# draft11_proto.net
KiCad netlist of a schematic drawn in EAGLE
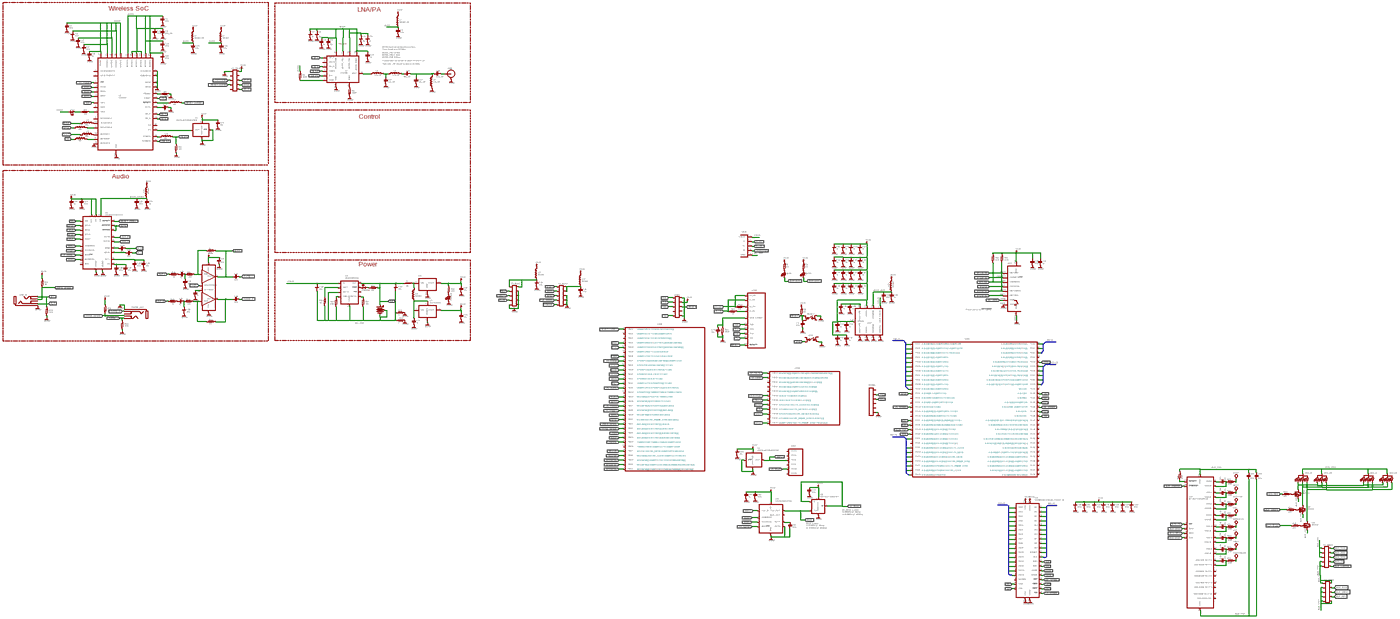
[diagram p0: schematic, sheet 1, overview]
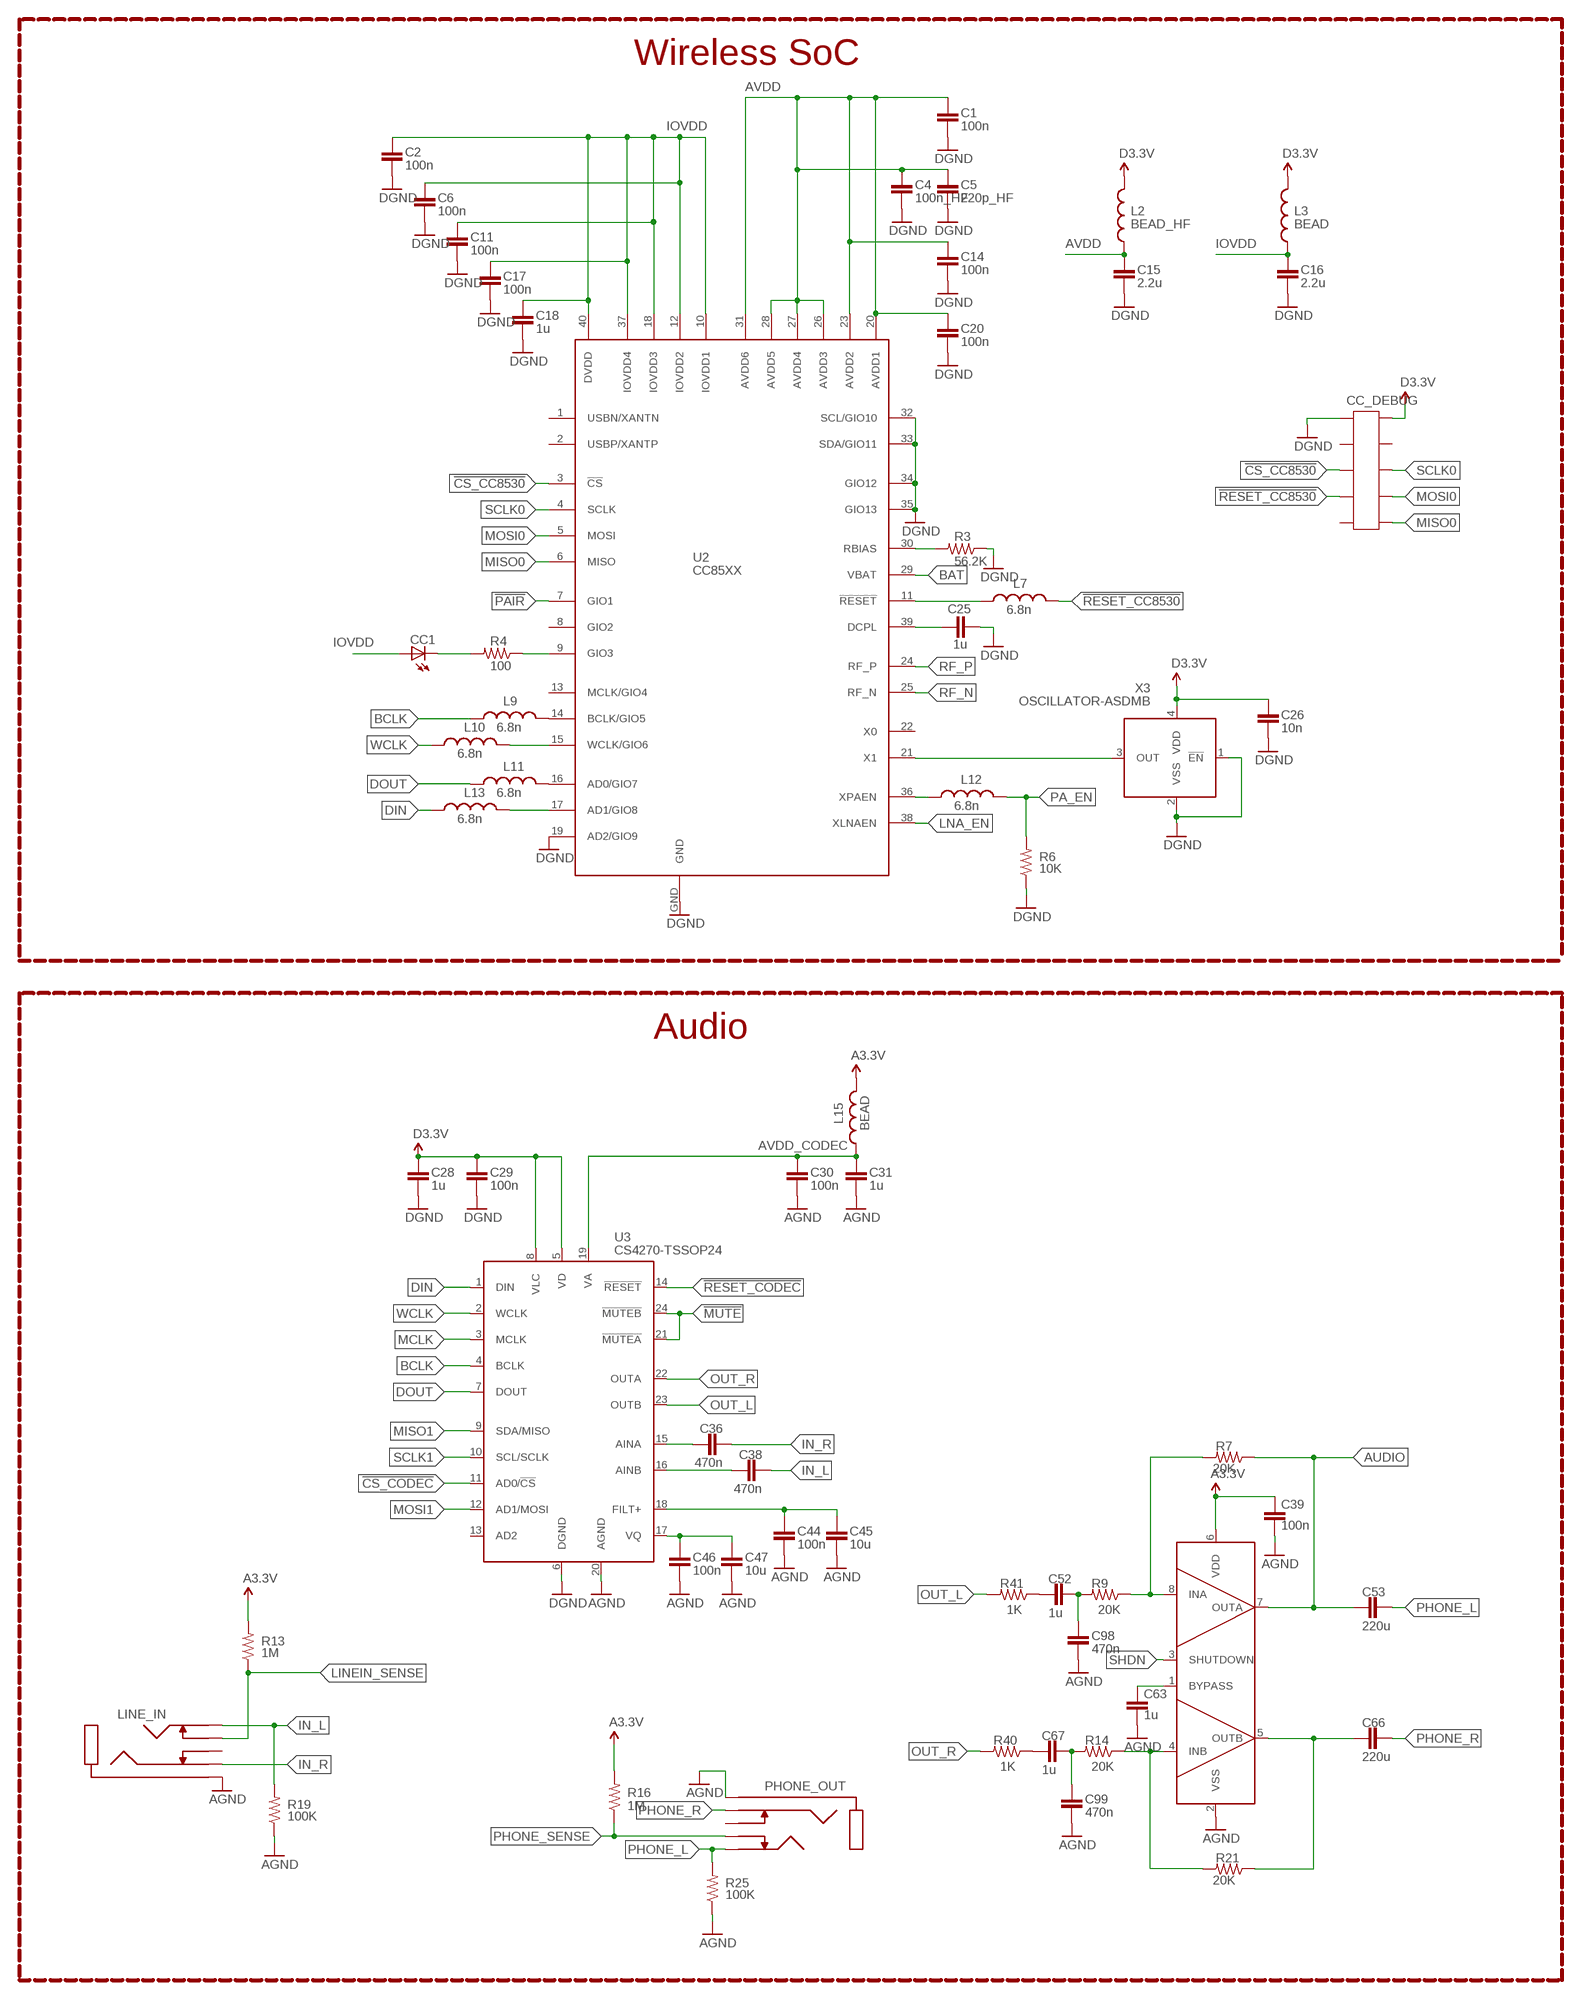
[diagram p1: schematic, sheet 1, part 1 of 4]
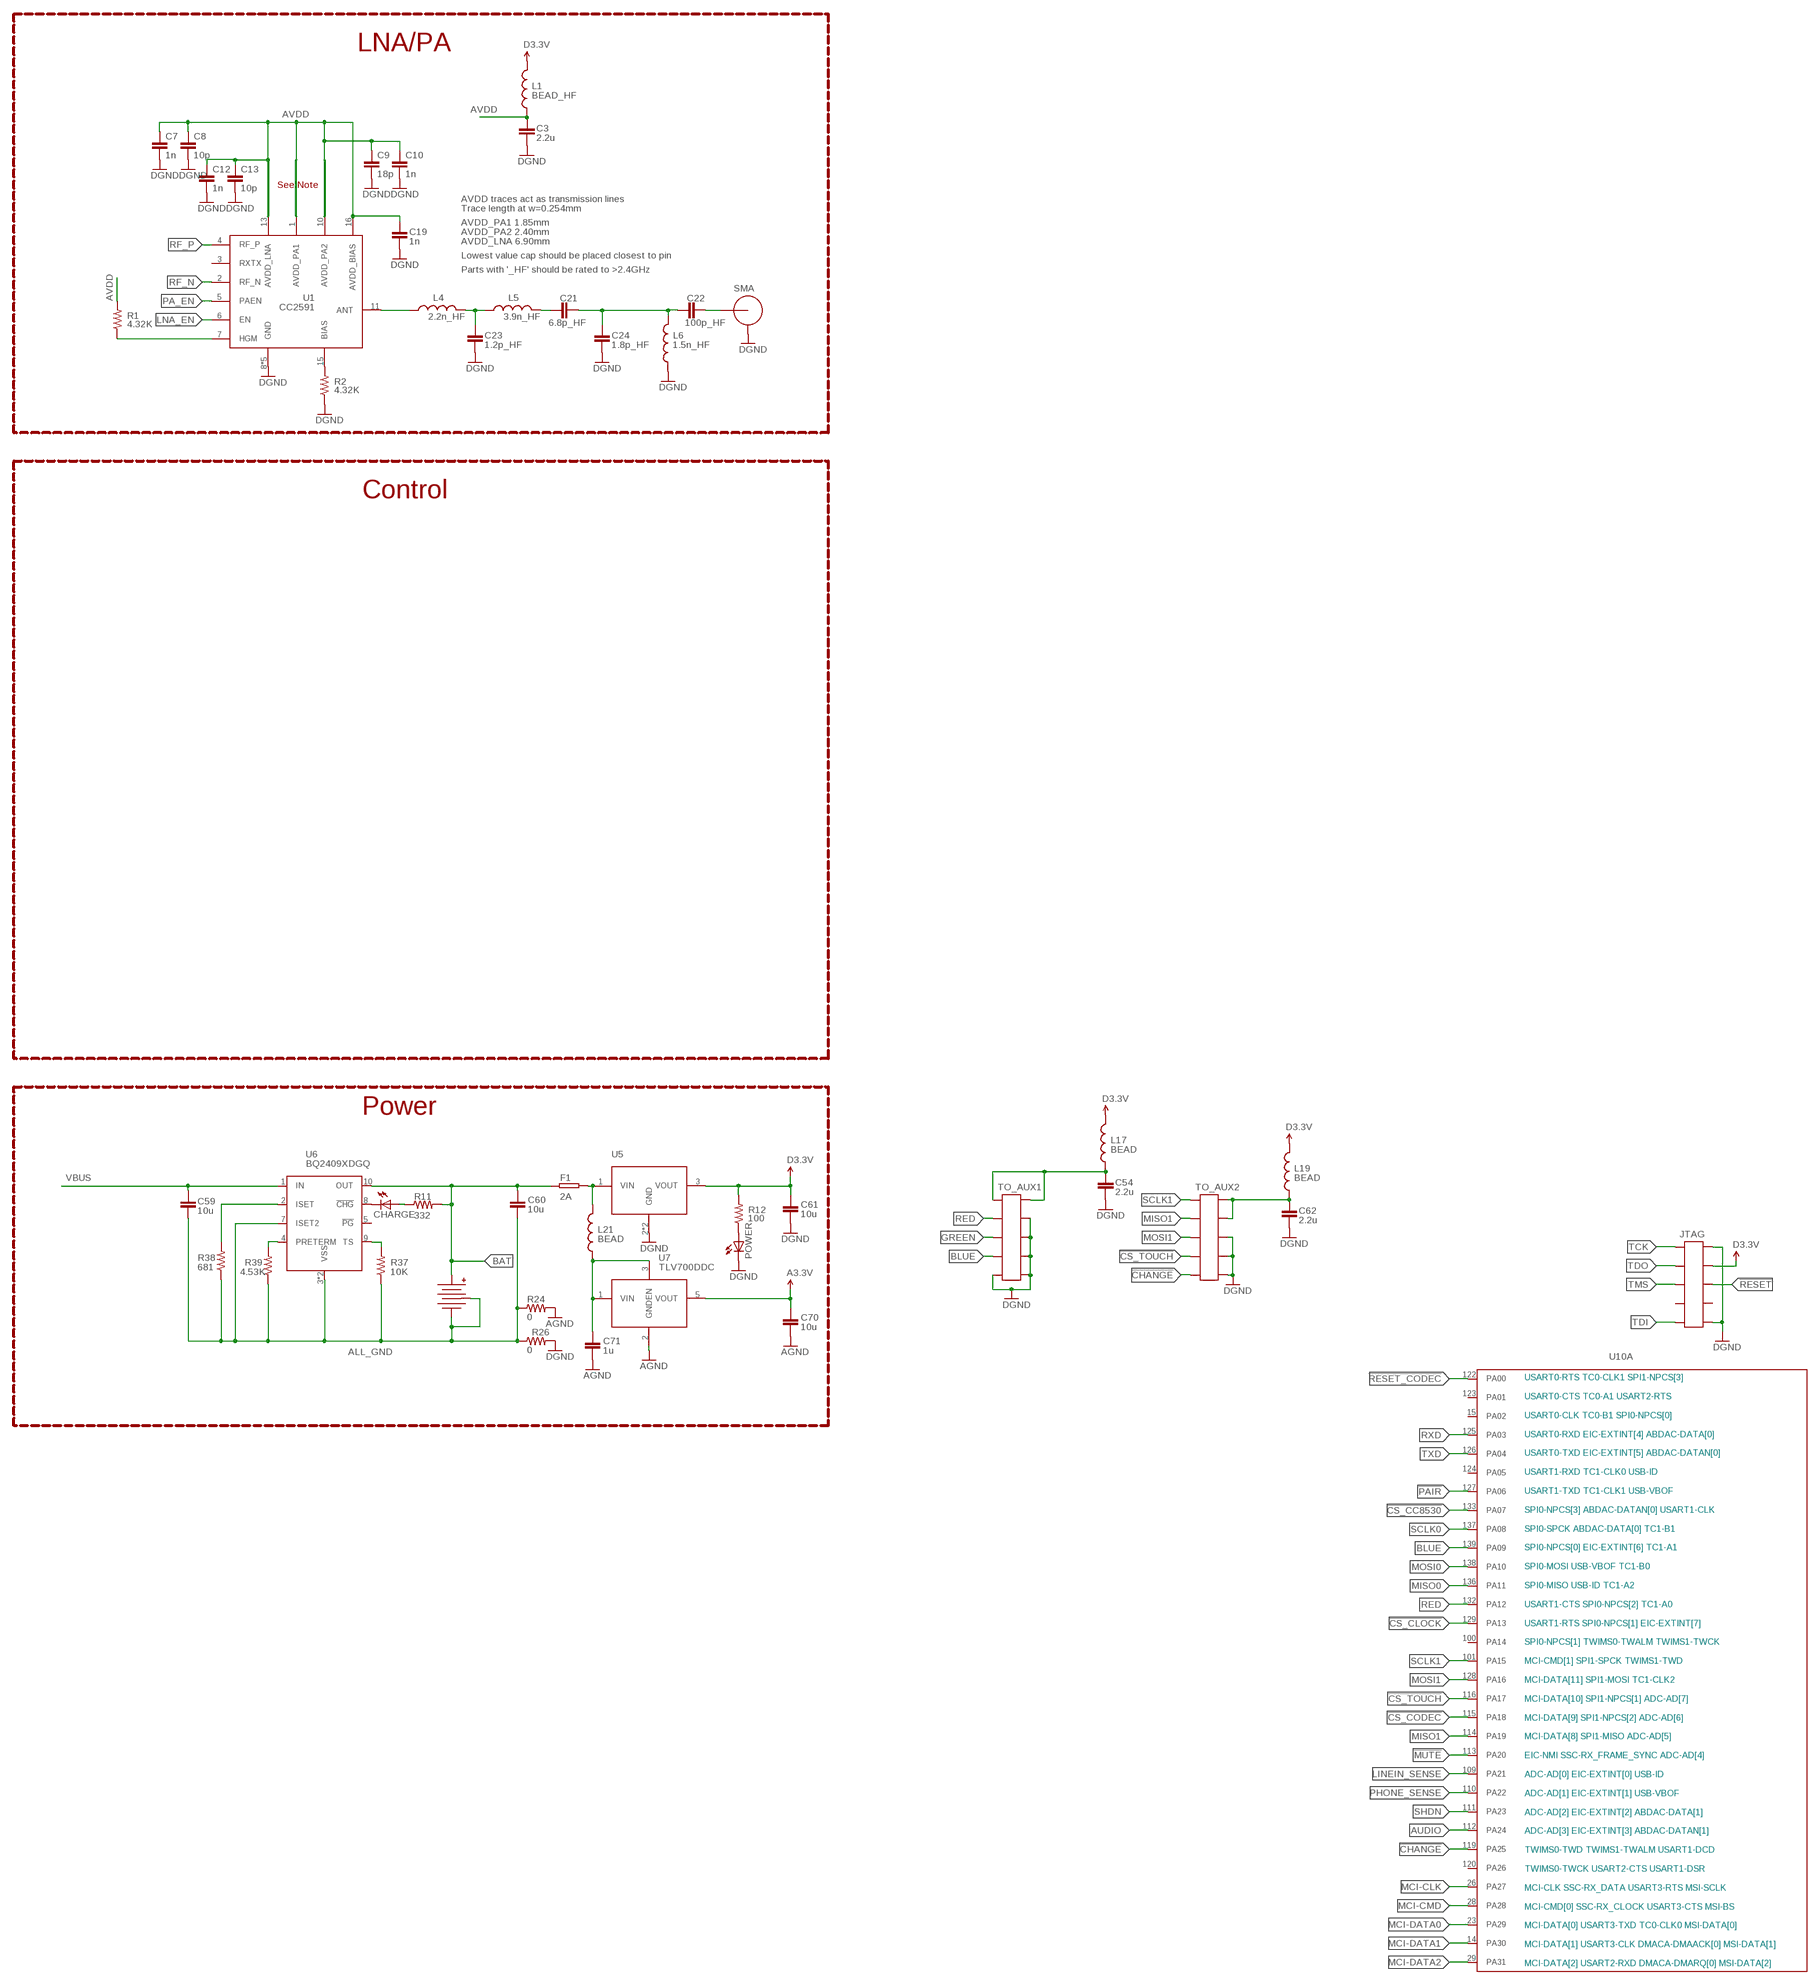
[diagram p2: schematic, sheet 1, part 2 of 4]
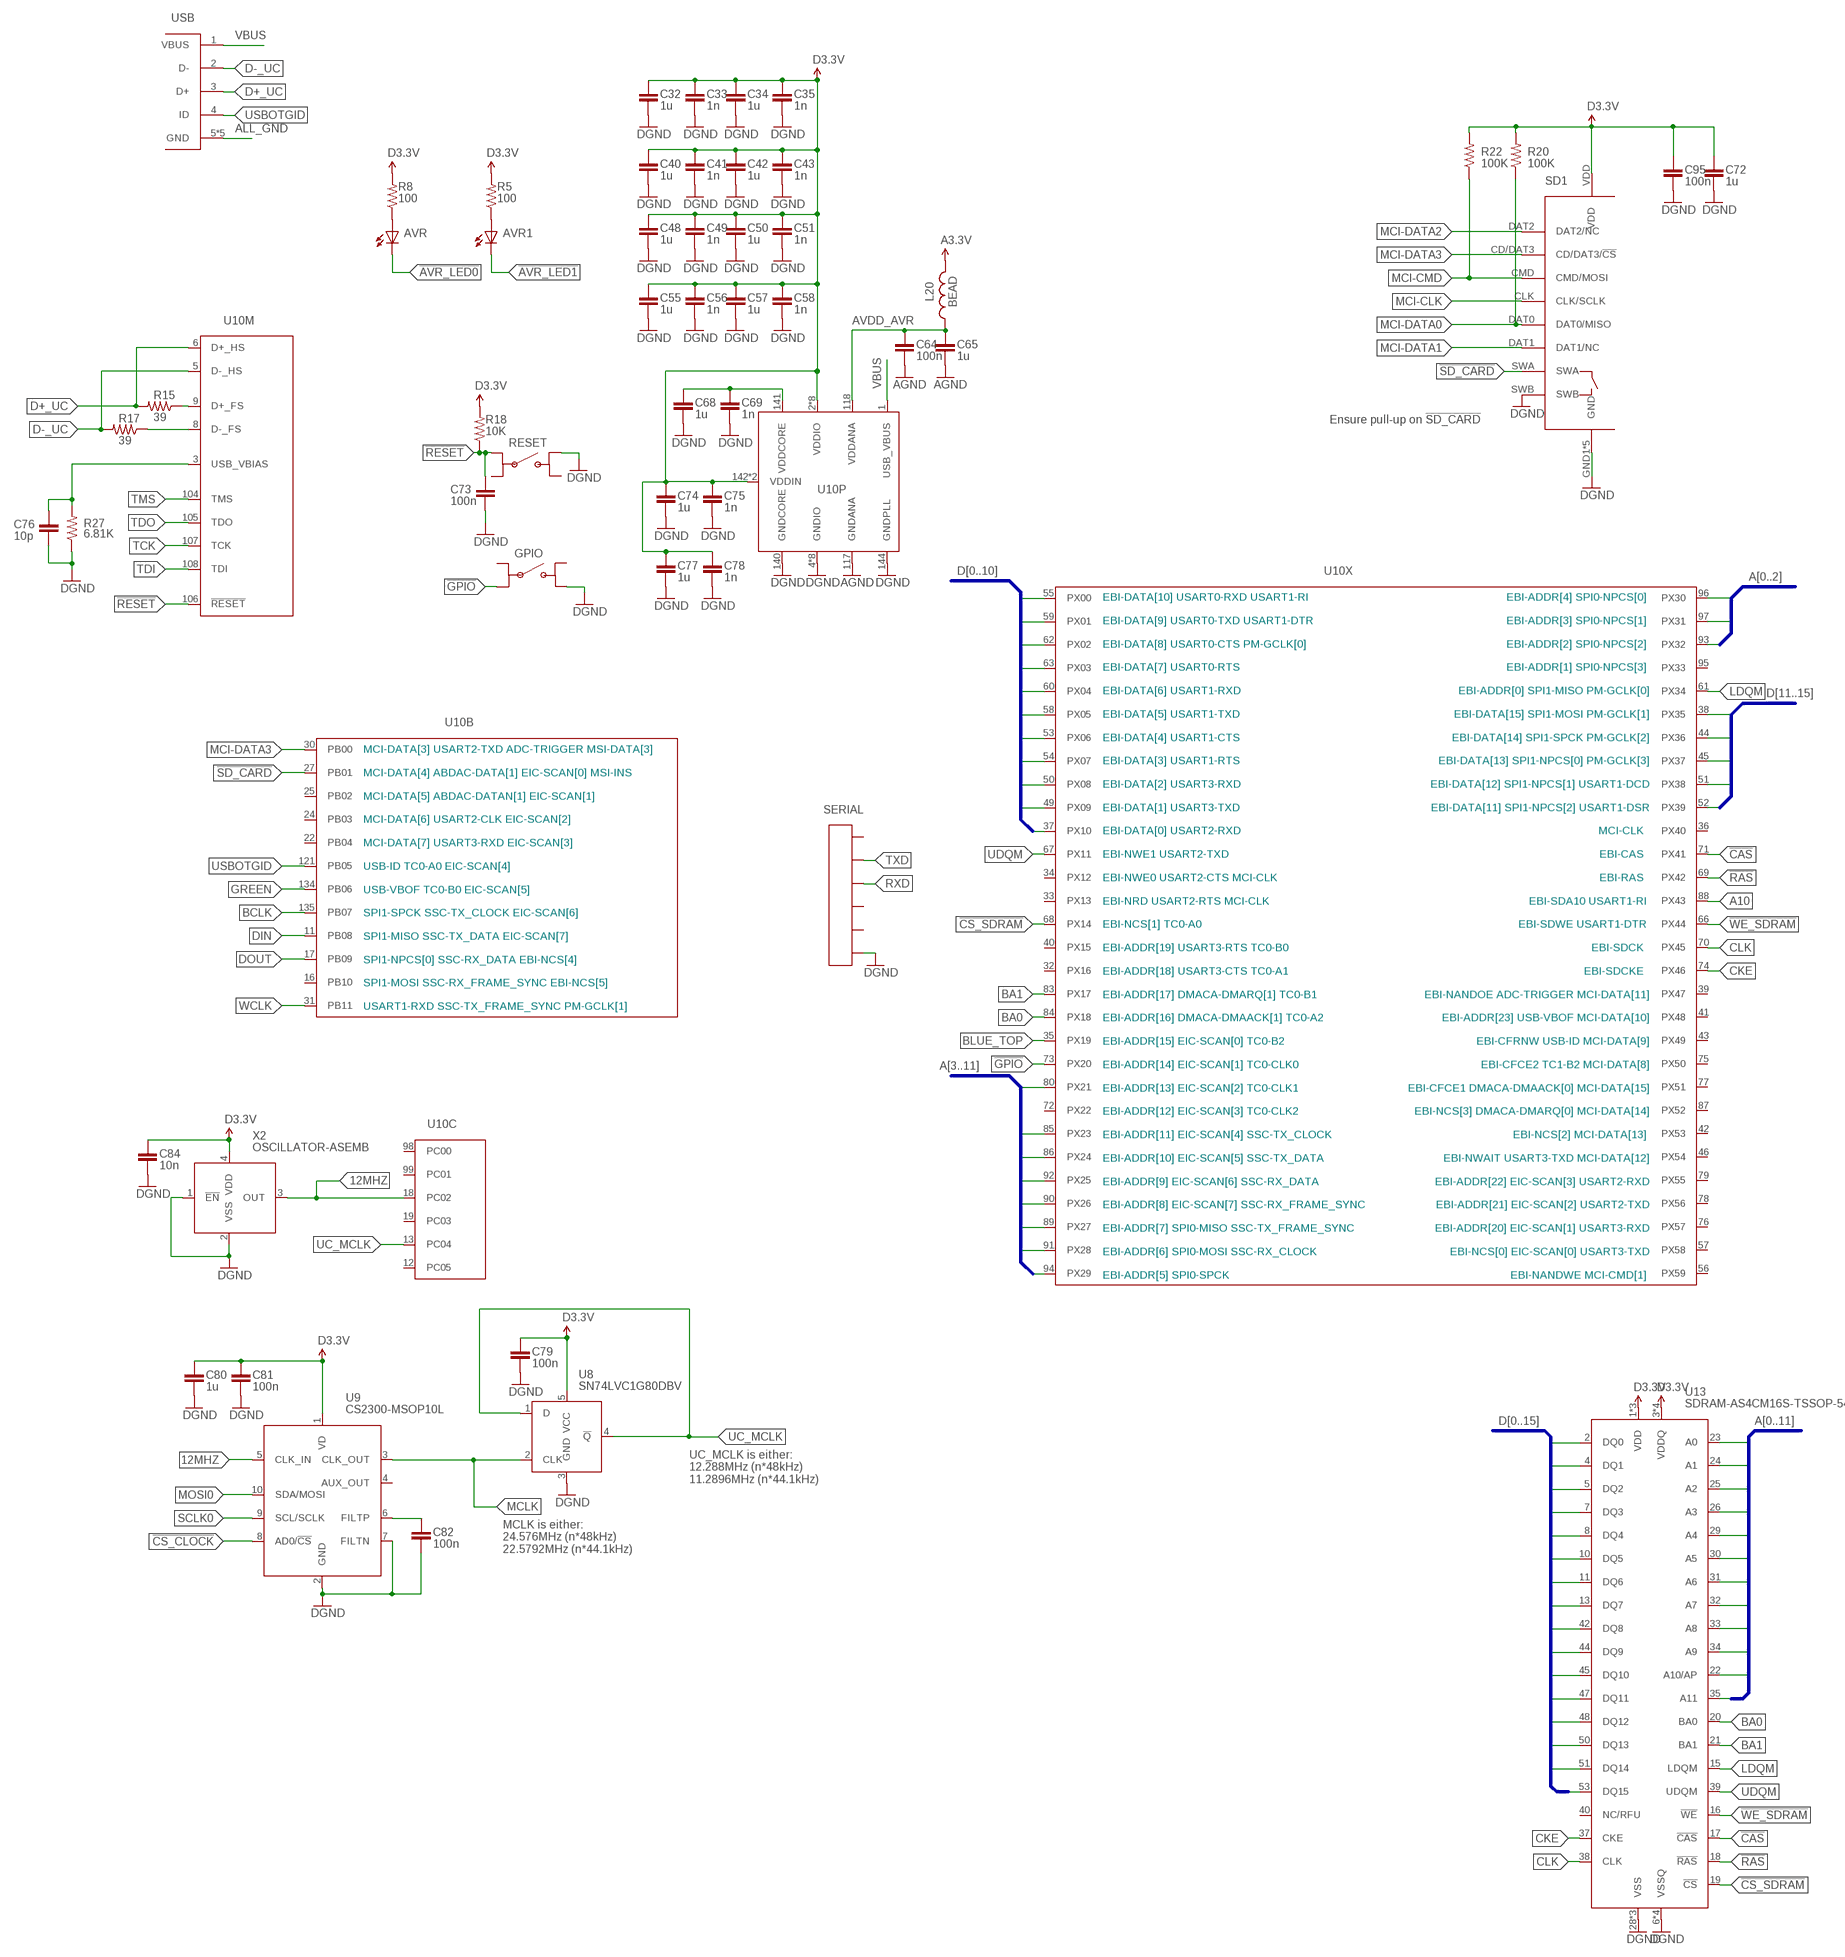
[diagram p3: schematic, sheet 1, part 3 of 4]
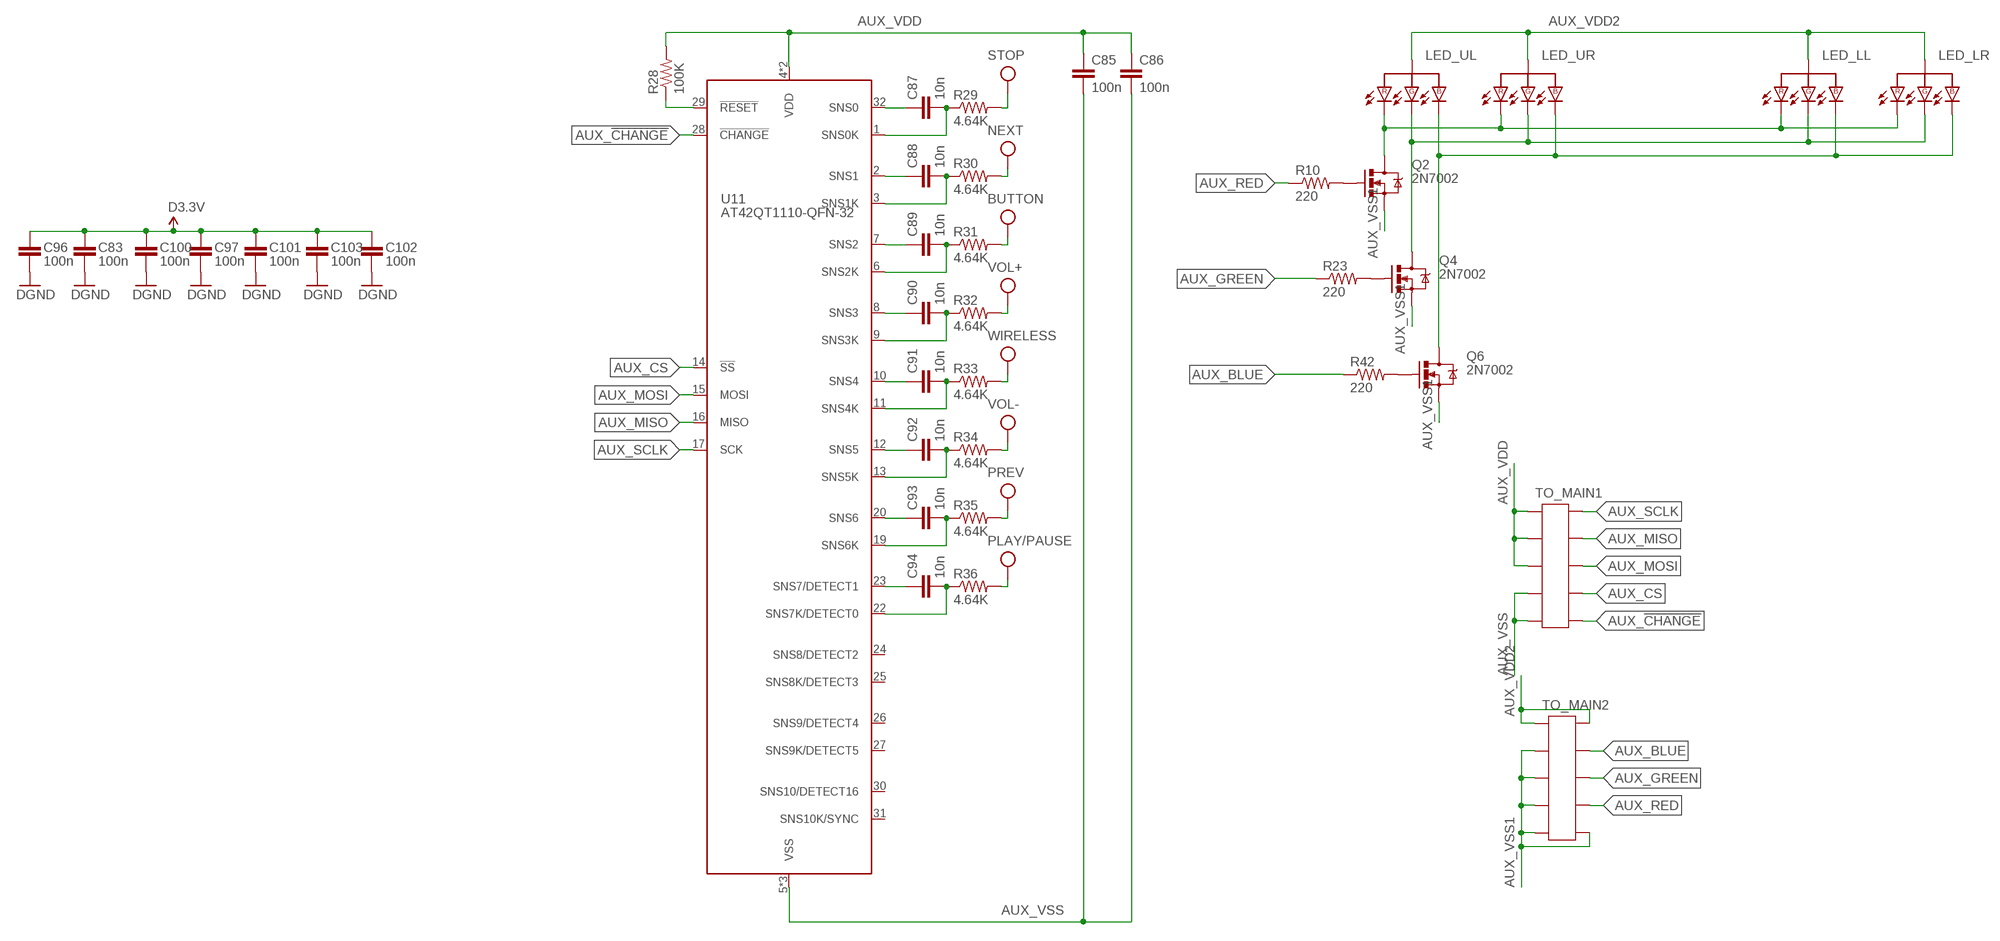
[diagram p4: schematic, sheet 1, part 4 of 4]

(export (version "E")
  (design (tool "Eeschema 10.0.6"))
  (components
    (comp (ref "AVR")
      (value "LED1206")
      (footprint "eagle-import:LED-1206")
      (libsource (lib "eagle-import") (part "LED1206"))
    )
    (comp (ref "AVR1")
      (value "LED1206")
      (footprint "eagle-import:LED-1206")
      (libsource (lib "eagle-import") (part "LED1206"))
    )
    (comp (ref "BATTERY")
      (value "BATTERY-LIPO-JST")
      (footprint "eagle-import:1775469-2")
      (libsource (lib "eagle-import") (part "BATTERY-LIPO-JST"))
    )
    (comp (ref "BUTTON")
      (value "TOUCH_PAD-CIRCLE-10MM")
      (footprint "eagle-import:TOUCH-CIRCLE-10MM")
      (libsource (lib "eagle-import") (part "TOUCH_PAD-CIRCLE-10MM"))
    )
    (comp (ref "C1")
      (value "100n")
      (footprint "eagle-import:C0603")
      (libsource (lib "eagle-import") (part "C-EUC0603"))
    )
    (comp (ref "C2")
      (value "100n")
      (footprint "eagle-import:C0603")
      (libsource (lib "eagle-import") (part "C-EUC0603"))
    )
    (comp (ref "C3")
      (value "2.2u")
      (footprint "eagle-import:C0603")
      (libsource (lib "eagle-import") (part "C-EUC0603"))
    )
    (comp (ref "C4")
      (value "100n_HF")
      (footprint "eagle-import:C0603")
      (libsource (lib "eagle-import") (part "C-EUC0603"))
    )
    (comp (ref "C5")
      (value "220p_HF")
      (footprint "eagle-import:C0603")
      (libsource (lib "eagle-import") (part "C-EUC0603"))
    )
    (comp (ref "C6")
      (value "100n")
      (footprint "eagle-import:C0603")
      (libsource (lib "eagle-import") (part "C-EUC0603"))
    )
    (comp (ref "C7")
      (value "1n")
      (footprint "eagle-import:C0603")
      (libsource (lib "eagle-import") (part "C-EUC0603"))
    )
    (comp (ref "C8")
      (value "10p")
      (footprint "eagle-import:C0603")
      (libsource (lib "eagle-import") (part "C-EUC0603"))
    )
    (comp (ref "C9")
      (value "18p")
      (footprint "eagle-import:C0603")
      (libsource (lib "eagle-import") (part "C-EUC0603"))
    )
    (comp (ref "C10")
      (value "1n")
      (footprint "eagle-import:C0603")
      (libsource (lib "eagle-import") (part "C-EUC0603"))
    )
    (comp (ref "C11")
      (value "100n")
      (footprint "eagle-import:C0603")
      (libsource (lib "eagle-import") (part "C-EUC0603"))
    )
    (comp (ref "C12")
      (value "1n")
      (footprint "eagle-import:C0603")
      (libsource (lib "eagle-import") (part "C-EUC0603"))
    )
    (comp (ref "C13")
      (value "10p")
      (footprint "eagle-import:C0603")
      (libsource (lib "eagle-import") (part "C-EUC0603"))
    )
    (comp (ref "C14")
      (value "100n")
      (footprint "eagle-import:C0603")
      (libsource (lib "eagle-import") (part "C-EUC0603"))
    )
    (comp (ref "C15")
      (value "2.2u")
      (footprint "eagle-import:C0603")
      (libsource (lib "eagle-import") (part "C-EUC0603"))
    )
    (comp (ref "C16")
      (value "2.2u")
      (footprint "eagle-import:C0603")
      (libsource (lib "eagle-import") (part "C-EUC0603"))
    )
    (comp (ref "C17")
      (value "100n")
      (footprint "eagle-import:C0603")
      (libsource (lib "eagle-import") (part "C-EUC0603"))
    )
    (comp (ref "C18")
      (value "1u")
      (footprint "eagle-import:C0603")
      (libsource (lib "eagle-import") (part "C-EUC0603"))
    )
    (comp (ref "C19")
      (value "1n")
      (footprint "eagle-import:C0603")
      (libsource (lib "eagle-import") (part "C-EUC0603"))
    )
    (comp (ref "C20")
      (value "100n")
      (footprint "eagle-import:C0603")
      (libsource (lib "eagle-import") (part "C-EUC0603"))
    )
    (comp (ref "C21")
      (value "6.8p_HF")
      (footprint "eagle-import:C0603")
      (libsource (lib "eagle-import") (part "C-EUC0603"))
    )
    (comp (ref "C22")
      (value "100p_HF")
      (footprint "eagle-import:C0603")
      (libsource (lib "eagle-import") (part "C-EUC0603"))
    )
    (comp (ref "C23")
      (value "1.2p_HF")
      (footprint "eagle-import:C0603")
      (libsource (lib "eagle-import") (part "C-EUC0603"))
    )
    (comp (ref "C24")
      (value "1.8p_HF")
      (footprint "eagle-import:C0603")
      (libsource (lib "eagle-import") (part "C-EUC0603"))
    )
    (comp (ref "C25")
      (value "1u")
      (footprint "eagle-import:C0603")
      (libsource (lib "eagle-import") (part "C-EUC0603"))
    )
    (comp (ref "C26")
      (value "10n")
      (footprint "eagle-import:C0603")
      (libsource (lib "eagle-import") (part "C-EUC0603"))
    )
    (comp (ref "C28")
      (value "1u")
      (footprint "eagle-import:C0603")
      (libsource (lib "eagle-import") (part "C-EUC0603"))
    )
    (comp (ref "C29")
      (value "100n")
      (footprint "eagle-import:C0603")
      (libsource (lib "eagle-import") (part "C-EUC0603"))
    )
    (comp (ref "C30")
      (value "100n")
      (footprint "eagle-import:C0603")
      (libsource (lib "eagle-import") (part "C-EUC0603"))
    )
    (comp (ref "C31")
      (value "1u")
      (footprint "eagle-import:C0603")
      (libsource (lib "eagle-import") (part "C-EUC0603"))
    )
    (comp (ref "C32")
      (value "1u")
      (footprint "eagle-import:C0603")
      (libsource (lib "eagle-import") (part "C-EUC0603"))
    )
    (comp (ref "C33")
      (value "1n")
      (footprint "eagle-import:C0603")
      (libsource (lib "eagle-import") (part "C-EUC0603"))
    )
    (comp (ref "C34")
      (value "1u")
      (footprint "eagle-import:C0603")
      (libsource (lib "eagle-import") (part "C-EUC0603"))
    )
    (comp (ref "C35")
      (value "1n")
      (footprint "eagle-import:C0603")
      (libsource (lib "eagle-import") (part "C-EUC0603"))
    )
    (comp (ref "C36")
      (value "470n")
      (footprint "eagle-import:C0603")
      (libsource (lib "eagle-import") (part "C-EUC0603"))
    )
    (comp (ref "C38")
      (value "470n")
      (footprint "eagle-import:C0603")
      (libsource (lib "eagle-import") (part "C-EUC0603"))
    )
    (comp (ref "C39")
      (value "100n")
      (footprint "eagle-import:C0603")
      (libsource (lib "eagle-import") (part "C-EUC0603"))
    )
    (comp (ref "C40")
      (value "1u")
      (footprint "eagle-import:C0603")
      (libsource (lib "eagle-import") (part "C-EUC0603"))
    )
    (comp (ref "C41")
      (value "1n")
      (footprint "eagle-import:C0603")
      (libsource (lib "eagle-import") (part "C-EUC0603"))
    )
    (comp (ref "C42")
      (value "1u")
      (footprint "eagle-import:C0603")
      (libsource (lib "eagle-import") (part "C-EUC0603"))
    )
    (comp (ref "C43")
      (value "1n")
      (footprint "eagle-import:C0603")
      (libsource (lib "eagle-import") (part "C-EUC0603"))
    )
    (comp (ref "C44")
      (value "100n")
      (footprint "eagle-import:C0603")
      (libsource (lib "eagle-import") (part "C-EUC0603"))
    )
    (comp (ref "C45")
      (value "10u")
      (footprint "eagle-import:C0603")
      (libsource (lib "eagle-import") (part "C-EUC0603"))
    )
    (comp (ref "C46")
      (value "100n")
      (footprint "eagle-import:C0603")
      (libsource (lib "eagle-import") (part "C-EUC0603"))
    )
    (comp (ref "C47")
      (value "10u")
      (footprint "eagle-import:C0603")
      (libsource (lib "eagle-import") (part "C-EUC0603"))
    )
    (comp (ref "C48")
      (value "1u")
      (footprint "eagle-import:C0603")
      (libsource (lib "eagle-import") (part "C-EUC0603"))
    )
    (comp (ref "C49")
      (value "1n")
      (footprint "eagle-import:C0603")
      (libsource (lib "eagle-import") (part "C-EUC0603"))
    )
    (comp (ref "C50")
      (value "1u")
      (footprint "eagle-import:C0603")
      (libsource (lib "eagle-import") (part "C-EUC0603"))
    )
    (comp (ref "C51")
      (value "1n")
      (footprint "eagle-import:C0603")
      (libsource (lib "eagle-import") (part "C-EUC0603"))
    )
    (comp (ref "C52")
      (value "1u")
      (footprint "eagle-import:C0603")
      (libsource (lib "eagle-import") (part "C-EUC0603"))
    )
    (comp (ref "C53")
      (value "220u")
      (footprint "eagle-import:C1210")
      (libsource (lib "eagle-import") (part "C-EUC1210"))
    )
    (comp (ref "C54")
      (value "2.2u")
      (footprint "eagle-import:C0603")
      (libsource (lib "eagle-import") (part "C-EUC0603"))
    )
    (comp (ref "C55")
      (value "1u")
      (footprint "eagle-import:C0603")
      (libsource (lib "eagle-import") (part "C-EUC0603"))
    )
    (comp (ref "C56")
      (value "1n")
      (footprint "eagle-import:C0603")
      (libsource (lib "eagle-import") (part "C-EUC0603"))
    )
    (comp (ref "C57")
      (value "1u")
      (footprint "eagle-import:C0603")
      (libsource (lib "eagle-import") (part "C-EUC0603"))
    )
    (comp (ref "C58")
      (value "1n")
      (footprint "eagle-import:C0603")
      (libsource (lib "eagle-import") (part "C-EUC0603"))
    )
    (comp (ref "C59")
      (value "10u")
      (footprint "eagle-import:C0603")
      (libsource (lib "eagle-import") (part "C-EUC0603"))
    )
    (comp (ref "C60")
      (value "10u")
      (footprint "eagle-import:C0603")
      (libsource (lib "eagle-import") (part "C-EUC0603"))
    )
    (comp (ref "C61")
      (value "10u")
      (footprint "eagle-import:C0603")
      (libsource (lib "eagle-import") (part "C-EUC0603"))
    )
    (comp (ref "C62")
      (value "2.2u")
      (footprint "eagle-import:C0603")
      (libsource (lib "eagle-import") (part "C-EUC0603"))
    )
    (comp (ref "C63")
      (value "1u")
      (footprint "eagle-import:C0603")
      (libsource (lib "eagle-import") (part "C-EUC0603"))
    )
    (comp (ref "C64")
      (value "100n")
      (footprint "eagle-import:C0603")
      (libsource (lib "eagle-import") (part "C-EUC0603"))
    )
    (comp (ref "C65")
      (value "1u")
      (footprint "eagle-import:C0603")
      (libsource (lib "eagle-import") (part "C-EUC0603"))
    )
    (comp (ref "C66")
      (value "220u")
      (footprint "eagle-import:C1210")
      (libsource (lib "eagle-import") (part "C-EUC1210"))
    )
    (comp (ref "C67")
      (value "1u")
      (footprint "eagle-import:C0603")
      (libsource (lib "eagle-import") (part "C-EUC0603"))
    )
    (comp (ref "C68")
      (value "1u")
      (footprint "eagle-import:C0603")
      (libsource (lib "eagle-import") (part "C-EUC0603"))
    )
    (comp (ref "C69")
      (value "1n")
      (footprint "eagle-import:C0603")
      (libsource (lib "eagle-import") (part "C-EUC0603"))
    )
    (comp (ref "C70")
      (value "10u")
      (footprint "eagle-import:C0603@1")
      (libsource (lib "eagle-import") (part "rcl_C-EUC0603"))
    )
    (comp (ref "C71")
      (value "1u")
      (footprint "eagle-import:C0603")
      (libsource (lib "eagle-import") (part "C-EUC0603"))
    )
    (comp (ref "C72")
      (value "1u")
      (footprint "eagle-import:C0603")
      (libsource (lib "eagle-import") (part "C-EUC0603"))
    )
    (comp (ref "C73")
      (value "100n")
      (footprint "eagle-import:C0603")
      (libsource (lib "eagle-import") (part "C-EUC0603"))
    )
    (comp (ref "C74")
      (value "1u")
      (footprint "eagle-import:C0603")
      (libsource (lib "eagle-import") (part "C-EUC0603"))
    )
    (comp (ref "C75")
      (value "1n")
      (footprint "eagle-import:C0603")
      (libsource (lib "eagle-import") (part "C-EUC0603"))
    )
    (comp (ref "C76")
      (value "10p")
      (footprint "eagle-import:C0603")
      (libsource (lib "eagle-import") (part "C-EUC0603"))
    )
    (comp (ref "C77")
      (value "1u")
      (footprint "eagle-import:C0603")
      (libsource (lib "eagle-import") (part "C-EUC0603"))
    )
    (comp (ref "C78")
      (value "1n")
      (footprint "eagle-import:C0603")
      (libsource (lib "eagle-import") (part "C-EUC0603"))
    )
    (comp (ref "C79")
      (value "100n")
      (footprint "eagle-import:C0603")
      (libsource (lib "eagle-import") (part "C-EUC0603"))
    )
    (comp (ref "C80")
      (value "1u")
      (footprint "eagle-import:C0603")
      (libsource (lib "eagle-import") (part "C-EUC0603"))
    )
    (comp (ref "C81")
      (value "100n")
      (footprint "eagle-import:C0603")
      (libsource (lib "eagle-import") (part "C-EUC0603"))
    )
    (comp (ref "C82")
      (value "100n")
      (footprint "eagle-import:C0603")
      (libsource (lib "eagle-import") (part "C-EUC0603"))
    )
    (comp (ref "C83")
      (value "100n")
      (footprint "eagle-import:C0603")
      (libsource (lib "eagle-import") (part "C-EUC0603"))
    )
    (comp (ref "C84")
      (value "10n")
      (footprint "eagle-import:C0603")
      (libsource (lib "eagle-import") (part "C-EUC0603"))
    )
    (comp (ref "C85")
      (value "100n")
      (footprint "eagle-import:C0603")
      (libsource (lib "eagle-import") (part "C-EUC0603"))
    )
    (comp (ref "C86")
      (value "100n")
      (footprint "eagle-import:C0603")
      (libsource (lib "eagle-import") (part "C-EUC0603"))
    )
    (comp (ref "C87")
      (value "10n")
      (footprint "eagle-import:C0603")
      (libsource (lib "eagle-import") (part "C-EUC0603"))
    )
    (comp (ref "C88")
      (value "10n")
      (footprint "eagle-import:C0603")
      (libsource (lib "eagle-import") (part "C-EUC0603"))
    )
    (comp (ref "C89")
      (value "10n")
      (footprint "eagle-import:C0603")
      (libsource (lib "eagle-import") (part "C-EUC0603"))
    )
    (comp (ref "C90")
      (value "10n")
      (footprint "eagle-import:C0603")
      (libsource (lib "eagle-import") (part "C-EUC0603"))
    )
    (comp (ref "C91")
      (value "10n")
      (footprint "eagle-import:C0603")
      (libsource (lib "eagle-import") (part "C-EUC0603"))
    )
    (comp (ref "C92")
      (value "10n")
      (footprint "eagle-import:C0603")
      (libsource (lib "eagle-import") (part "C-EUC0603"))
    )
    (comp (ref "C93")
      (value "10n")
      (footprint "eagle-import:C0603")
      (libsource (lib "eagle-import") (part "C-EUC0603"))
    )
    (comp (ref "C94")
      (value "10n")
      (footprint "eagle-import:C0603")
      (libsource (lib "eagle-import") (part "C-EUC0603"))
    )
    (comp (ref "C95")
      (value "100n")
      (footprint "eagle-import:C0603")
      (libsource (lib "eagle-import") (part "C-EUC0603"))
    )
    (comp (ref "C96")
      (value "100n")
      (footprint "eagle-import:C0603")
      (libsource (lib "eagle-import") (part "C-EUC0603"))
    )
    (comp (ref "C97")
      (value "100n")
      (footprint "eagle-import:C0603")
      (libsource (lib "eagle-import") (part "C-EUC0603"))
    )
    (comp (ref "C98")
      (value "470n")
      (footprint "eagle-import:C0603")
      (libsource (lib "eagle-import") (part "C-EUC0603"))
    )
    (comp (ref "C99")
      (value "470n")
      (footprint "eagle-import:C0603")
      (libsource (lib "eagle-import") (part "C-EUC0603"))
    )
    (comp (ref "C100")
      (value "100n")
      (footprint "eagle-import:C0603")
      (libsource (lib "eagle-import") (part "C-EUC0603"))
    )
    (comp (ref "C101")
      (value "100n")
      (footprint "eagle-import:C0603")
      (libsource (lib "eagle-import") (part "C-EUC0603"))
    )
    (comp (ref "C102")
      (value "100n")
      (footprint "eagle-import:C0603")
      (libsource (lib "eagle-import") (part "C-EUC0603"))
    )
    (comp (ref "C103")
      (value "100n")
      (footprint "eagle-import:C0603")
      (libsource (lib "eagle-import") (part "C-EUC0603"))
    )
    (comp (ref "CC1")
      (value "LED1206")
      (footprint "eagle-import:LED-1206")
      (libsource (lib "eagle-import") (part "LED1206"))
    )
    (comp (ref "CC_DEBUG")
      (value "HEADER-10P-SMD-MALE2")
      (footprint "eagle-import:HEADER-10P-1.27MM")
      (libsource (lib "eagle-import") (part "HEADER-10P-SMD-MALE2"))
    )
    (comp (ref "CHARGE")
      (value "LED1206")
      (footprint "eagle-import:LED-1206")
      (libsource (lib "eagle-import") (part "LED1206"))
    )
    (comp (ref "F1")
      (value "2A")
      (footprint "eagle-import:1210")
      (libsource (lib "eagle-import") (part "PTC_FUSE"))
    )
    (comp (ref "GPIO")
      (value "TACT_SWITCH-PTS-525")
      (footprint "eagle-import:PTS-525")
      (libsource (lib "eagle-import") (part "TACT_SWITCH-PTS-525"))
    )
    (comp (ref "JTAG")
      (value "HEADER-10P-SMD-MALE2")
      (footprint "eagle-import:HEADER-10P-1.27MM")
      (libsource (lib "eagle-import") (part "HEADER-10P-SMD-MALE2"))
    )
    (comp (ref "L1")
      (value "BEAD_HF")
      (footprint "eagle-import:0603")
      (libsource (lib "eagle-import") (part "INDUCTOR0603"))
    )
    (comp (ref "L2")
      (value "BEAD_HF")
      (footprint "eagle-import:0603")
      (libsource (lib "eagle-import") (part "INDUCTOR0603"))
    )
    (comp (ref "L3")
      (value "BEAD")
      (footprint "eagle-import:0603")
      (libsource (lib "eagle-import") (part "INDUCTOR0603"))
    )
    (comp (ref "L4")
      (value "2.2n_HF")
      (footprint "eagle-import:0603")
      (libsource (lib "eagle-import") (part "INDUCTOR0603"))
    )
    (comp (ref "L5")
      (value "3.9n_HF")
      (footprint "eagle-import:0603")
      (libsource (lib "eagle-import") (part "INDUCTOR0603"))
    )
    (comp (ref "L6")
      (value "1.5n_HF")
      (footprint "eagle-import:0603")
      (libsource (lib "eagle-import") (part "INDUCTOR0603"))
    )
    (comp (ref "L7")
      (value "6.8n")
      (footprint "eagle-import:0603")
      (libsource (lib "eagle-import") (part "INDUCTOR0603"))
    )
    (comp (ref "L9")
      (value "6.8n")
      (footprint "eagle-import:0603")
      (libsource (lib "eagle-import") (part "INDUCTOR0603"))
    )
    (comp (ref "L10")
      (value "6.8n")
      (footprint "eagle-import:0603")
      (libsource (lib "eagle-import") (part "INDUCTOR0603"))
    )
    (comp (ref "L11")
      (value "6.8n")
      (footprint "eagle-import:0603")
      (libsource (lib "eagle-import") (part "INDUCTOR0603"))
    )
    (comp (ref "L12")
      (value "6.8n")
      (footprint "eagle-import:0603@1")
      (libsource (lib "eagle-import") (part "SparkFun-Passives_INDUCTOR0603"))
    )
    (comp (ref "L13")
      (value "6.8n")
      (footprint "eagle-import:0603")
      (libsource (lib "eagle-import") (part "INDUCTOR0603"))
    )
    (comp (ref "L15")
      (value "BEAD")
      (footprint "eagle-import:0603@1")
      (libsource (lib "eagle-import") (part "SparkFun-Passives_INDUCTOR0603"))
    )
    (comp (ref "L17")
      (value "BEAD")
      (footprint "eagle-import:0603")
      (libsource (lib "eagle-import") (part "INDUCTOR0603"))
    )
    (comp (ref "L19")
      (value "BEAD")
      (footprint "eagle-import:0603")
      (libsource (lib "eagle-import") (part "INDUCTOR0603"))
    )
    (comp (ref "L20")
      (value "BEAD")
      (footprint "eagle-import:0603")
      (libsource (lib "eagle-import") (part "INDUCTOR0603"))
    )
    (comp (ref "L21")
      (value "BEAD")
      (footprint "eagle-import:0603")
      (libsource (lib "eagle-import") (part "INDUCTOR0603"))
    )
    (comp (ref "LED_LL")
      (value "LED_RGB")
      (footprint "eagle-import:PLCC-4")
      (libsource (lib "eagle-import") (part "LED_RGB"))
    )
    (comp (ref "LED_LR")
      (value "LED_RGB")
      (footprint "eagle-import:PLCC-4")
      (libsource (lib "eagle-import") (part "LED_RGB"))
    )
    (comp (ref "LED_UL")
      (value "LED_RGB")
      (footprint "eagle-import:PLCC-4")
      (libsource (lib "eagle-import") (part "LED_RGB"))
    )
    (comp (ref "LED_UR")
      (value "LED_RGB")
      (footprint "eagle-import:PLCC-4")
      (libsource (lib "eagle-import") (part "LED_RGB"))
    )
    (comp (ref "LINE_IN")
      (value "PHONE_SW-STX-35332-5N")
      (footprint "eagle-import:STX-35332-5N")
      (libsource (lib "eagle-import") (part "PHONE_SW-STX-35332-5N"))
    )
    (comp (ref "NEXT")
      (value "TOUCH_PAD-CIRCLE-10MM")
      (footprint "eagle-import:TOUCH-CIRCLE-10MM")
      (libsource (lib "eagle-import") (part "TOUCH_PAD-CIRCLE-10MM"))
    )
    (comp (ref "PHONE_OUT")
      (value "PHONE_SW-STX-35332-5N")
      (footprint "eagle-import:STX-35332-5N")
      (libsource (lib "eagle-import") (part "PHONE_SW-STX-35332-5N"))
    )
    (comp (ref "PLAY/PAUSE")
      (value "TOUCH_PAD-CIRCLE-10MM")
      (footprint "eagle-import:TOUCH-CIRCLE-10MM")
      (libsource (lib "eagle-import") (part "TOUCH_PAD-CIRCLE-10MM"))
    )
    (comp (ref "POWER")
      (value "LED1206")
      (footprint "eagle-import:LED-1206")
      (libsource (lib "eagle-import") (part "LED1206"))
    )
    (comp (ref "PREV")
      (value "TOUCH_PAD-CIRCLE-10MM")
      (footprint "eagle-import:TOUCH-CIRCLE-10MM")
      (libsource (lib "eagle-import") (part "TOUCH_PAD-CIRCLE-10MM"))
    )
    (comp (ref "Q2")
      (value "2N7002")
      (footprint "eagle-import:SOT23-3")
      (libsource (lib "eagle-import") (part "MOSFET-NCHANNELSMD"))
    )
    (comp (ref "Q4")
      (value "2N7002")
      (footprint "eagle-import:SOT23-3")
      (libsource (lib "eagle-import") (part "MOSFET-NCHANNELSMD"))
    )
    (comp (ref "Q6")
      (value "2N7002")
      (footprint "eagle-import:SOT23-3")
      (libsource (lib "eagle-import") (part "MOSFET-NCHANNELSMD"))
    )
    (comp (ref "R1")
      (value "4.32K")
      (footprint "eagle-import:R0603")
      (libsource (lib "eagle-import") (part "R-US_R0603"))
    )
    (comp (ref "R2")
      (value "4.32K")
      (footprint "eagle-import:R0603")
      (libsource (lib "eagle-import") (part "R-US_R0603"))
    )
    (comp (ref "R3")
      (value "56.2K")
      (footprint "eagle-import:R0603")
      (libsource (lib "eagle-import") (part "R-US_R0603"))
    )
    (comp (ref "R4")
      (value "100")
      (footprint "eagle-import:R0603")
      (libsource (lib "eagle-import") (part "R-US_R0603"))
    )
    (comp (ref "R5")
      (value "100")
      (footprint "eagle-import:R0603")
      (libsource (lib "eagle-import") (part "R-US_R0603"))
    )
    (comp (ref "R6")
      (value "10K")
      (footprint "eagle-import:R0603")
      (libsource (lib "eagle-import") (part "R-US_R0603"))
    )
    (comp (ref "R7")
      (value "20K")
      (footprint "eagle-import:R0603")
      (libsource (lib "eagle-import") (part "R-US_R0603"))
    )
    (comp (ref "R8")
      (value "100")
      (footprint "eagle-import:R0603")
      (libsource (lib "eagle-import") (part "R-US_R0603"))
    )
    (comp (ref "R9")
      (value "20K")
      (footprint "eagle-import:R0603")
      (libsource (lib "eagle-import") (part "R-US_R0603"))
    )
    (comp (ref "R10")
      (value "220")
      (footprint "eagle-import:R0603")
      (libsource (lib "eagle-import") (part "R-US_R0603"))
    )
    (comp (ref "R11")
      (value "332")
      (footprint "eagle-import:R0603")
      (libsource (lib "eagle-import") (part "R-US_R0603"))
    )
    (comp (ref "R12")
      (value "100")
      (footprint "eagle-import:R0603")
      (libsource (lib "eagle-import") (part "R-US_R0603"))
    )
    (comp (ref "R13")
      (value "1M")
      (footprint "eagle-import:R0603")
      (libsource (lib "eagle-import") (part "R-US_R0603"))
    )
    (comp (ref "R14")
      (value "20K")
      (footprint "eagle-import:R0603")
      (libsource (lib "eagle-import") (part "R-US_R0603"))
    )
    (comp (ref "R15")
      (value "39")
      (footprint "eagle-import:R0603")
      (libsource (lib "eagle-import") (part "R-US_R0603"))
    )
    (comp (ref "R16")
      (value "1M")
      (footprint "eagle-import:R0603")
      (libsource (lib "eagle-import") (part "R-US_R0603"))
    )
    (comp (ref "R17")
      (value "39")
      (footprint "eagle-import:R0603")
      (libsource (lib "eagle-import") (part "R-US_R0603"))
    )
    (comp (ref "R18")
      (value "10K")
      (footprint "eagle-import:R0603")
      (libsource (lib "eagle-import") (part "R-US_R0603"))
    )
    (comp (ref "R19")
      (value "100K")
      (footprint "eagle-import:R0603")
      (libsource (lib "eagle-import") (part "R-US_R0603"))
    )
    (comp (ref "R20")
      (value "100K")
      (footprint "eagle-import:R0603")
      (libsource (lib "eagle-import") (part "R-US_R0603"))
    )
    (comp (ref "R21")
      (value "20K")
      (footprint "eagle-import:R0603")
      (libsource (lib "eagle-import") (part "R-US_R0603"))
    )
    (comp (ref "R22")
      (value "100K")
      (footprint "eagle-import:R0603")
      (libsource (lib "eagle-import") (part "R-US_R0603"))
    )
    (comp (ref "R23")
      (value "220")
      (footprint "eagle-import:R0603")
      (libsource (lib "eagle-import") (part "R-US_R0603"))
    )
    (comp (ref "R24")
      (value "0")
      (footprint "eagle-import:R0603")
      (libsource (lib "eagle-import") (part "R-US_R0603"))
    )
    (comp (ref "R25")
      (value "100K")
      (footprint "eagle-import:R0603")
      (libsource (lib "eagle-import") (part "R-US_R0603"))
    )
    (comp (ref "R26")
      (value "0")
      (footprint "eagle-import:R0603")
      (libsource (lib "eagle-import") (part "R-US_R0603"))
    )
    (comp (ref "R27")
      (value "6.81K")
      (footprint "eagle-import:R0603")
      (libsource (lib "eagle-import") (part "R-US_R0603"))
    )
    (comp (ref "R28")
      (value "100K")
      (footprint "eagle-import:R0603")
      (libsource (lib "eagle-import") (part "R-US_R0603"))
    )
    (comp (ref "R29")
      (value "4.64K")
      (footprint "eagle-import:R0603")
      (libsource (lib "eagle-import") (part "R-US_R0603"))
    )
    (comp (ref "R30")
      (value "4.64K")
      (footprint "eagle-import:R0603")
      (libsource (lib "eagle-import") (part "R-US_R0603"))
    )
    (comp (ref "R31")
      (value "4.64K")
      (footprint "eagle-import:R0603")
      (libsource (lib "eagle-import") (part "R-US_R0603"))
    )
    (comp (ref "R32")
      (value "4.64K")
      (footprint "eagle-import:R0603")
      (libsource (lib "eagle-import") (part "R-US_R0603"))
    )
    (comp (ref "R33")
      (value "4.64K")
      (footprint "eagle-import:R0603")
      (libsource (lib "eagle-import") (part "R-US_R0603"))
    )
    (comp (ref "R34")
      (value "4.64K")
      (footprint "eagle-import:R0603")
      (libsource (lib "eagle-import") (part "R-US_R0603"))
    )
    (comp (ref "R35")
      (value "4.64K")
      (footprint "eagle-import:R0603")
      (libsource (lib "eagle-import") (part "R-US_R0603"))
    )
    (comp (ref "R36")
      (value "4.64K")
      (footprint "eagle-import:R0603")
      (libsource (lib "eagle-import") (part "R-US_R0603"))
    )
    (comp (ref "R37")
      (value "10K")
      (footprint "eagle-import:R0603")
      (libsource (lib "eagle-import") (part "R-US_R0603"))
    )
    (comp (ref "R38")
      (value "681")
      (footprint "eagle-import:R0603")
      (libsource (lib "eagle-import") (part "R-US_R0603"))
    )
    (comp (ref "R39")
      (value "4.53K")
      (footprint "eagle-import:R0603")
      (libsource (lib "eagle-import") (part "R-US_R0603"))
    )
    (comp (ref "R40")
      (value "1K")
      (footprint "eagle-import:R0603")
      (libsource (lib "eagle-import") (part "R-US_R0603"))
    )
    (comp (ref "R41")
      (value "1K")
      (footprint "eagle-import:R0603")
      (libsource (lib "eagle-import") (part "R-US_R0603"))
    )
    (comp (ref "R42")
      (value "220")
      (footprint "eagle-import:R0603")
      (libsource (lib "eagle-import") (part "R-US_R0603"))
    )
    (comp (ref "RESET")
      (value "TACT_SWITCH-PTS-525")
      (footprint "eagle-import:PTS-525")
      (libsource (lib "eagle-import") (part "TACT_SWITCH-PTS-525"))
    )
    (comp (ref "SD1")
      (value "MICROSD104031-0811")
      (footprint "eagle-import:MOLEX_104031-0811")
      (libsource (lib "eagle-import") (part "MICROSD104031-0811"))
    )
    (comp (ref "SERIAL")
      (value "HEADER-6X1-961106-5500")
      (footprint "eagle-import:HEADER-3M-961-6P-2.54MM")
      (libsource (lib "eagle-import") (part "HEADER-6X1-961106-5500"))
    )
    (comp (ref "SMA")
      (value "SMA-REVSMA-0.62")
      (footprint "eagle-import:CONREVSMA003.062")
      (libsource (lib "eagle-import") (part "SMA-REVSMA-0.62"))
    )
    (comp (ref "STOP")
      (value "TOUCH_PAD-CIRCLE-10MM")
      (footprint "eagle-import:TOUCH-CIRCLE-10MM")
      (libsource (lib "eagle-import") (part "TOUCH_PAD-CIRCLE-10MM"))
    )
    (comp (ref "TO_AUX1")
      (value "HEADER-10P-SMD-2MM-FEMALE")
      (footprint "eagle-import:M22-63405")
      (libsource (lib "eagle-import") (part "HEADER-10P-SMD-2MM-FEMALE"))
    )
    (comp (ref "TO_AUX2")
      (value "HEADER-10P-SMD-2MM-FEMALE")
      (footprint "eagle-import:M22-63405")
      (libsource (lib "eagle-import") (part "HEADER-10P-SMD-2MM-FEMALE"))
    )
    (comp (ref "TO_MAIN1")
      (value "HEADER-10P-SMD-2MM-MALE")
      (footprint "eagle-import:M22-53205")
      (libsource (lib "eagle-import") (part "HEADER-10P-SMD-2MM-MALE"))
    )
    (comp (ref "TO_MAIN2")
      (value "HEADER-10P-SMD-2MM-MALE")
      (footprint "eagle-import:M22-53205")
      (libsource (lib "eagle-import") (part "HEADER-10P-SMD-2MM-MALE"))
    )
    (comp (ref "U1")
      (value "CC2591")
      (footprint "eagle-import:S-PVQFN-N16")
      (libsource (lib "eagle-import") (part "CC2591"))
    )
    (comp (ref "U2")
      (value "CC85XX")
      (footprint "eagle-import:S-PVQFN-N40")
      (libsource (lib "eagle-import") (part "CC85XX"))
    )
    (comp (ref "U3")
      (value "CS4270-TSSOP24")
      (footprint "eagle-import:TSSOP-24L")
      (libsource (lib "eagle-import") (part "CS4270-TSSOP24"))
    )
    (comp (ref "U4")
      (value "LM4881")
      (footprint "eagle-import:SO08")
      (libsource (lib "eagle-import") (part "LM4881"))
    )
    (comp (ref "U5")
      (value "MCP1826-SOT223")
      (footprint "eagle-import:SOT-223")
      (libsource (lib "eagle-import") (part "MCP1826-SOT223"))
    )
    (comp (ref "U6")
      (value "BQ2409XDGQ")
      (footprint "eagle-import:S-PDSO-G10")
      (libsource (lib "eagle-import") (part "BQ2409XDGQ"))
    )
    (comp (ref "U7")
      (value "TLV700DDC")
      (footprint "eagle-import:SOT-23-5")
      (libsource (lib "eagle-import") (part "TLV700DDC"))
    )
    (comp (ref "U8")
      (value "SN74LVC1G80DBV")
      (footprint "eagle-import:SOT-23-5")
      (libsource (lib "eagle-import") (part "SN74LVC1G80DBV"))
    )
    (comp (ref "U9")
      (value "CS2300-MSOP10L")
      (footprint "eagle-import:MSOP-10L")
      (libsource (lib "eagle-import") (part "CS2300-MSOP10L"))
    )
    (comp (ref "U10")
      (value "AT32UC3A3-LQFP-144")
      (footprint "eagle-import:LQFP-144")
      (libsource (lib "eagle-import") (part "AT32UC3A3-LQFP-144"))
    )
    (comp (ref "U11")
      (value "AT42QT1110-QFN-32")
      (footprint "eagle-import:QFN-32")
      (libsource (lib "eagle-import") (part "AT42QT1110-QFN-32"))
    )
    (comp (ref "U13")
      (value "SDRAM-AS4CM16S-TSSOP-54")
      (footprint "eagle-import:TSSOP-54")
      (libsource (lib "eagle-import") (part "SDRAM-AS4CM16S-TSSOP-54"))
    )
    (comp (ref "USB")
      (value "USB_MICRO_AB")
      (footprint "eagle-import:USB_MICRO_AB")
      (libsource (lib "eagle-import") (part "USB_MICRO_AB"))
    )
    (comp (ref "VOL+")
      (value "TOUCH_PAD-CIRCLE-10MM")
      (footprint "eagle-import:TOUCH-CIRCLE-10MM")
      (libsource (lib "eagle-import") (part "TOUCH_PAD-CIRCLE-10MM"))
    )
    (comp (ref "VOL-")
      (value "TOUCH_PAD-CIRCLE-10MM")
      (footprint "eagle-import:TOUCH-CIRCLE-10MM")
      (libsource (lib "eagle-import") (part "TOUCH_PAD-CIRCLE-10MM"))
    )
    (comp (ref "WIRELESS")
      (value "TOUCH_PAD-CIRCLE-10MM")
      (footprint "eagle-import:TOUCH-CIRCLE-10MM")
      (libsource (lib "eagle-import") (part "TOUCH_PAD-CIRCLE-10MM"))
    )
    (comp (ref "X2")
      (value "OSCILLATOR-ASEMB")
      (footprint "eagle-import:ASEMB")
      (libsource (lib "eagle-import") (part "OSCILLATOR-ASEMB"))
    )
    (comp (ref "X3")
      (value "OSCILLATOR-ASDMB")
      (footprint "eagle-import:ASDMB")
      (libsource (lib "eagle-import") (part "OSCILLATOR-ASDMB"))
    )
  )
  (nets
    (net (code "1") (name "/A0") (class "Default")
      (node (ref "U10") (pin "93") (pinfunction "PX32_93") (pintype "bidirectional"))
      (node (ref "U13") (pin "23") (pinfunction "A0_23") (pintype "bidirectional"))
    )
    (net (code "2") (name "/A1") (class "Default")
      (node (ref "U10") (pin "97") (pinfunction "PX31_97") (pintype "bidirectional"))
      (node (ref "U13") (pin "24") (pinfunction "A1_24") (pintype "bidirectional"))
    )
    (net (code "3") (name "/A2") (class "Default")
      (node (ref "U10") (pin "96") (pinfunction "PX30_96") (pintype "bidirectional"))
      (node (ref "U13") (pin "25") (pinfunction "A2_25") (pintype "bidirectional"))
    )
    (net (code "4") (name "/A3") (class "Default")
      (node (ref "U10") (pin "94") (pinfunction "PX29_94") (pintype "bidirectional"))
      (node (ref "U13") (pin "26") (pinfunction "A3_26") (pintype "bidirectional"))
    )
    (net (code "5") (name "/A4") (class "Default")
      (node (ref "U10") (pin "91") (pinfunction "PX28_91") (pintype "bidirectional"))
      (node (ref "U13") (pin "29") (pinfunction "A4_29") (pintype "bidirectional"))
    )
    (net (code "6") (name "/A5") (class "Default")
      (node (ref "U10") (pin "89") (pinfunction "PX27_89") (pintype "bidirectional"))
      (node (ref "U13") (pin "30") (pinfunction "A5_30") (pintype "bidirectional"))
    )
    (net (code "7") (name "/A6") (class "Default")
      (node (ref "U10") (pin "90") (pinfunction "PX26_90") (pintype "bidirectional"))
      (node (ref "U13") (pin "31") (pinfunction "A6_31") (pintype "bidirectional"))
    )
    (net (code "8") (name "/A7") (class "Default")
      (node (ref "U10") (pin "92") (pinfunction "PX25_92") (pintype "bidirectional"))
      (node (ref "U13") (pin "32") (pinfunction "A7_32") (pintype "bidirectional"))
    )
    (net (code "9") (name "/A8") (class "Default")
      (node (ref "U10") (pin "86") (pinfunction "PX24_86") (pintype "bidirectional"))
      (node (ref "U13") (pin "33") (pinfunction "A8_33") (pintype "bidirectional"))
    )
    (net (code "10") (name "/A9") (class "Default")
      (node (ref "U10") (pin "85") (pinfunction "PX23_85") (pintype "bidirectional"))
      (node (ref "U13") (pin "34") (pinfunction "A9_34") (pintype "bidirectional"))
    )
    (net (code "11") (name "/A11") (class "Default")
      (node (ref "U10") (pin "80") (pinfunction "PX21_80") (pintype "bidirectional"))
      (node (ref "U13") (pin "35") (pinfunction "A11_35") (pintype "bidirectional"))
    )
    (net (code "12") (name "/ALL_GND") (class "Default")
      (node (ref "BATTERY") (pin "-") (pinfunction "N_-") (pintype "passive"))
      (node (ref "BATTERY") (pin "X1") (pinfunction "CASE_X1") (pintype "passive"))
      (node (ref "BATTERY") (pin "X2") (pinfunction "CASE_X2") (pintype "passive"))
      (node (ref "C59") (pin "2") (pinfunction "2_2") (pintype "passive"))
      (node (ref "C60") (pin "2") (pinfunction "2_2") (pintype "passive"))
      (node (ref "R24") (pin "1") (pinfunction "1_1") (pintype "passive"))
      (node (ref "R26") (pin "1") (pinfunction "1_1") (pintype "passive"))
      (node (ref "R37") (pin "1") (pinfunction "1_1") (pintype "passive"))
      (node (ref "R38") (pin "1") (pinfunction "1_1") (pintype "passive"))
      (node (ref "R39") (pin "1") (pinfunction "1_1") (pintype "passive"))
      (node (ref "U6") (pin "3") (pinfunction "VSS_3") (pintype "bidirectional"))
      (node (ref "U6") (pin "7") (pinfunction "ISET2_7") (pintype "bidirectional"))
      (node (ref "U6") (pin "GND") (pinfunction "VSS_GND") (pintype "bidirectional"))
      (node (ref "USB") (pin "5") (pinfunction "GND_5") (pintype "bidirectional"))
      (node (ref "USB") (pin "GND1") (pinfunction "GND_GND1") (pintype "bidirectional"))
      (node (ref "USB") (pin "GND2") (pinfunction "GND_GND2") (pintype "bidirectional"))
      (node (ref "USB") (pin "GND3") (pinfunction "GND_GND3") (pintype "bidirectional"))
      (node (ref "USB") (pin "GND4") (pinfunction "GND_GND4") (pintype "bidirectional"))
    )
    (net (code "13") (name "/AUX_VDD") (class "Default")
      (node (ref "C85") (pin "1") (pinfunction "1_1") (pintype "passive"))
      (node (ref "C86") (pin "1") (pinfunction "1_1") (pintype "passive"))
      (node (ref "R28") (pin "2") (pinfunction "2_2") (pintype "passive"))
      (node (ref "TO_MAIN1") (pin "1") (pinfunction "1_1") (pintype "bidirectional"))
      (node (ref "TO_MAIN1") (pin "3") (pinfunction "3_3") (pintype "bidirectional"))
      (node (ref "TO_MAIN1") (pin "5") (pinfunction "5_5") (pintype "bidirectional"))
      (node (ref "U11") (pin "18") (pinfunction "VDD_18") (pintype "bidirectional"))
      (node (ref "U11") (pin "4") (pinfunction "VDD_4") (pintype "bidirectional"))
    )
    (net (code "14") (name "/AUX_VDD2") (class "Default")
      (node (ref "LED_LL") (pin "2") (pinfunction "A_2") (pintype "passive"))
      (node (ref "LED_LL") (pin "2-2") (pinfunction "A_2-2") (pintype "passive"))
      (node (ref "LED_LR") (pin "2") (pinfunction "A_2") (pintype "passive"))
      (node (ref "LED_LR") (pin "2-2") (pinfunction "A_2-2") (pintype "passive"))
      (node (ref "LED_UL") (pin "2") (pinfunction "A_2") (pintype "passive"))
      (node (ref "LED_UL") (pin "2-2") (pinfunction "A_2-2") (pintype "passive"))
      (node (ref "LED_UR") (pin "2") (pinfunction "A_2") (pintype "passive"))
      (node (ref "LED_UR") (pin "2-2") (pinfunction "A_2-2") (pintype "passive"))
      (node (ref "TO_MAIN2") (pin "1") (pinfunction "1_1") (pintype "bidirectional"))
      (node (ref "TO_MAIN2") (pin "2") (pinfunction "2_2") (pintype "bidirectional"))
    )
    (net (code "15") (name "/AUX_VSS") (class "Default")
      (node (ref "C85") (pin "2") (pinfunction "2_2") (pintype "passive"))
      (node (ref "C86") (pin "2") (pinfunction "2_2") (pintype "passive"))
      (node (ref "TO_MAIN1") (pin "7") (pinfunction "7_7") (pintype "bidirectional"))
      (node (ref "TO_MAIN1") (pin "9") (pinfunction "9_9") (pintype "bidirectional"))
      (node (ref "U11") (pin "21") (pinfunction "VSS_21") (pintype "bidirectional"))
      (node (ref "U11") (pin "5") (pinfunction "VSS_5") (pintype "bidirectional"))
      (node (ref "U11") (pin "GND") (pinfunction "VSS_GND") (pintype "bidirectional"))
    )
    (net (code "16") (name "/AUX_VSS1") (class "Default")
      (node (ref "Q2") (pin "2") (pinfunction "S_2") (pintype "passive"))
      (node (ref "Q4") (pin "2") (pinfunction "S_2") (pintype "passive"))
      (node (ref "Q6") (pin "2") (pinfunction "S_2") (pintype "passive"))
      (node (ref "TO_MAIN2") (pin "10") (pinfunction "10_10") (pintype "bidirectional"))
      (node (ref "TO_MAIN2") (pin "3") (pinfunction "3_3") (pintype "bidirectional"))
      (node (ref "TO_MAIN2") (pin "5") (pinfunction "5_5") (pintype "bidirectional"))
      (node (ref "TO_MAIN2") (pin "7") (pinfunction "7_7") (pintype "bidirectional"))
      (node (ref "TO_MAIN2") (pin "9") (pinfunction "9_9") (pintype "bidirectional"))
    )
    (net (code "17") (name "/AUX_~{CHANGE}") (class "Default")
      (node (ref "TO_MAIN1") (pin "10") (pinfunction "10_10") (pintype "bidirectional"))
      (node (ref "U11") (pin "28") (pinfunction "~{CHANGE}_28") (pintype "bidirectional"))
    )
    (net (code "18") (name "/AVDD") (class "Default")
      (node (ref "C1") (pin "1") (pinfunction "1_1") (pintype "passive"))
      (node (ref "C10") (pin "1") (pinfunction "1_1") (pintype "passive"))
      (node (ref "C12") (pin "1") (pinfunction "1_1") (pintype "passive"))
      (node (ref "C13") (pin "1") (pinfunction "1_1") (pintype "passive"))
      (node (ref "C14") (pin "1") (pinfunction "1_1") (pintype "passive"))
      (node (ref "C15") (pin "1") (pinfunction "1_1") (pintype "passive"))
      (node (ref "C19") (pin "1") (pinfunction "1_1") (pintype "passive"))
      (node (ref "C20") (pin "1") (pinfunction "1_1") (pintype "passive"))
      (node (ref "C3") (pin "1") (pinfunction "1_1") (pintype "passive"))
      (node (ref "C4") (pin "1") (pinfunction "1_1") (pintype "passive"))
      (node (ref "C5") (pin "1") (pinfunction "1_1") (pintype "passive"))
      (node (ref "C7") (pin "1") (pinfunction "1_1") (pintype "passive"))
      (node (ref "C8") (pin "1") (pinfunction "1_1") (pintype "passive"))
      (node (ref "C9") (pin "1") (pinfunction "1_1") (pintype "passive"))
      (node (ref "L1") (pin "1") (pinfunction "1_1") (pintype "passive"))
      (node (ref "L2") (pin "1") (pinfunction "1_1") (pintype "passive"))
      (node (ref "R1") (pin "2") (pinfunction "2_2") (pintype "passive"))
      (node (ref "U1") (pin "1") (pinfunction "AVDD_PA1_1") (pintype "bidirectional"))
      (node (ref "U1") (pin "10") (pinfunction "AVDD_PA2_10") (pintype "bidirectional"))
      (node (ref "U1") (pin "13") (pinfunction "AVDD_LNA_13") (pintype "bidirectional"))
      (node (ref "U1") (pin "16") (pinfunction "AVDD_BIAS_16") (pintype "bidirectional"))
      (node (ref "U2") (pin "20") (pinfunction "AVDD1_20") (pintype "bidirectional"))
      (node (ref "U2") (pin "23") (pinfunction "AVDD2_23") (pintype "bidirectional"))
      (node (ref "U2") (pin "26") (pinfunction "AVDD3_26") (pintype "bidirectional"))
      (node (ref "U2") (pin "27") (pinfunction "AVDD4_27") (pintype "bidirectional"))
      (node (ref "U2") (pin "28") (pinfunction "AVDD5_28") (pintype "bidirectional"))
      (node (ref "U2") (pin "31") (pinfunction "AVDD6_31") (pintype "bidirectional"))
    )
    (net (code "19") (name "/AVDD_AVR") (class "Default")
      (node (ref "C64") (pin "1") (pinfunction "1_1") (pintype "passive"))
      (node (ref "C65") (pin "1") (pinfunction "1_1") (pintype "passive"))
      (node (ref "L20") (pin "1") (pinfunction "1_1") (pintype "passive"))
      (node (ref "U10") (pin "118") (pinfunction "VDDANA_118") (pintype "bidirectional"))
    )
    (net (code "20") (name "/AVDD_CODEC") (class "Default")
      (node (ref "C30") (pin "1") (pinfunction "1_1") (pintype "passive"))
      (node (ref "C31") (pin "1") (pinfunction "1_1") (pintype "passive"))
      (node (ref "L15") (pin "1") (pinfunction "1_1") (pintype "passive"))
      (node (ref "U3") (pin "19") (pinfunction "VA_19") (pintype "bidirectional"))
    )
    (net (code "24") (name "/D0") (class "Default")
      (node (ref "U10") (pin "37") (pinfunction "PX10_37") (pintype "bidirectional"))
      (node (ref "U13") (pin "2") (pinfunction "DQ0_2") (pintype "bidirectional"))
    )
    (net (code "25") (name "/D1") (class "Default")
      (node (ref "U10") (pin "49") (pinfunction "PX09_49") (pintype "bidirectional"))
      (node (ref "U13") (pin "4") (pinfunction "DQ1_4") (pintype "bidirectional"))
    )
    (net (code "26") (name "/D2") (class "Default")
      (node (ref "U10") (pin "50") (pinfunction "PX08_50") (pintype "bidirectional"))
      (node (ref "U13") (pin "5") (pinfunction "DQ2_5") (pintype "bidirectional"))
    )
    (net (code "27") (name "/D3") (class "Default")
      (node (ref "U10") (pin "54") (pinfunction "PX07_54") (pintype "bidirectional"))
      (node (ref "U13") (pin "7") (pinfunction "DQ3_7") (pintype "bidirectional"))
    )
    (net (code "28") (name "/D4") (class "Default")
      (node (ref "U10") (pin "53") (pinfunction "PX06_53") (pintype "bidirectional"))
      (node (ref "U13") (pin "8") (pinfunction "DQ4_8") (pintype "bidirectional"))
    )
    (net (code "29") (name "/D5") (class "Default")
      (node (ref "U10") (pin "58") (pinfunction "PX05_58") (pintype "bidirectional"))
      (node (ref "U13") (pin "10") (pinfunction "DQ5_10") (pintype "bidirectional"))
    )
    (net (code "30") (name "/D6") (class "Default")
      (node (ref "U10") (pin "60") (pinfunction "PX04_60") (pintype "bidirectional"))
      (node (ref "U13") (pin "11") (pinfunction "DQ6_11") (pintype "bidirectional"))
    )
    (net (code "31") (name "/D7") (class "Default")
      (node (ref "U10") (pin "63") (pinfunction "PX03_63") (pintype "bidirectional"))
      (node (ref "U13") (pin "13") (pinfunction "DQ7_13") (pintype "bidirectional"))
    )
    (net (code "32") (name "/D8") (class "Default")
      (node (ref "U10") (pin "62") (pinfunction "PX02_62") (pintype "bidirectional"))
      (node (ref "U13") (pin "42") (pinfunction "DQ8_42") (pintype "bidirectional"))
    )
    (net (code "33") (name "/D9") (class "Default")
      (node (ref "U10") (pin "59") (pinfunction "PX01_59") (pintype "bidirectional"))
      (node (ref "U13") (pin "44") (pinfunction "DQ9_44") (pintype "bidirectional"))
    )
    (net (code "34") (name "/D10") (class "Default")
      (node (ref "U10") (pin "55") (pinfunction "PX00_55") (pintype "bidirectional"))
      (node (ref "U13") (pin "45") (pinfunction "DQ10_45") (pintype "bidirectional"))
    )
    (net (code "35") (name "/D11") (class "Default")
      (node (ref "U10") (pin "52") (pinfunction "PX39_52") (pintype "bidirectional"))
      (node (ref "U13") (pin "47") (pinfunction "DQ11_47") (pintype "bidirectional"))
    )
    (net (code "36") (name "/D12") (class "Default")
      (node (ref "U10") (pin "51") (pinfunction "PX38_51") (pintype "bidirectional"))
      (node (ref "U13") (pin "48") (pinfunction "DQ12_48") (pintype "bidirectional"))
    )
    (net (code "37") (name "/D13") (class "Default")
      (node (ref "U10") (pin "45") (pinfunction "PX37_45") (pintype "bidirectional"))
      (node (ref "U13") (pin "50") (pinfunction "DQ13_50") (pintype "bidirectional"))
    )
    (net (code "38") (name "/D14") (class "Default")
      (node (ref "U10") (pin "44") (pinfunction "PX36_44") (pintype "bidirectional"))
      (node (ref "U13") (pin "51") (pinfunction "DQ14_51") (pintype "bidirectional"))
    )
    (net (code "39") (name "/D15") (class "Default")
      (node (ref "U10") (pin "38") (pinfunction "PX35_38") (pintype "bidirectional"))
      (node (ref "U13") (pin "53") (pinfunction "DQ15_53") (pintype "bidirectional"))
    )
    (net (code "43") (name "/IOVDD") (class "Default")
      (node (ref "C11") (pin "1") (pinfunction "1_1") (pintype "passive"))
      (node (ref "C16") (pin "1") (pinfunction "1_1") (pintype "passive"))
      (node (ref "C17") (pin "1") (pinfunction "1_1") (pintype "passive"))
      (node (ref "C18") (pin "1") (pinfunction "1_1") (pintype "passive"))
      (node (ref "C2") (pin "1") (pinfunction "1_1") (pintype "passive"))
      (node (ref "C6") (pin "1") (pinfunction "1_1") (pintype "passive"))
      (node (ref "CC1") (pin "A") (pinfunction "A_A") (pintype "passive"))
      (node (ref "L3") (pin "1") (pinfunction "1_1") (pintype "passive"))
      (node (ref "U2") (pin "10") (pinfunction "IOVDD1_10") (pintype "bidirectional"))
      (node (ref "U2") (pin "12") (pinfunction "IOVDD2_12") (pintype "bidirectional"))
      (node (ref "U2") (pin "18") (pinfunction "IOVDD3_18") (pintype "bidirectional"))
      (node (ref "U2") (pin "37") (pinfunction "IOVDD4_37") (pintype "bidirectional"))
      (node (ref "U2") (pin "40") (pinfunction "DVDD_40") (pintype "bidirectional"))
    )
    (net (code "44") (name "/VBUS") (class "Default")
      (node (ref "C59") (pin "1") (pinfunction "1_1") (pintype "passive"))
      (node (ref "U10") (pin "1") (pinfunction "USB_VBUS_1") (pintype "bidirectional"))
      (node (ref "U6") (pin "1") (pinfunction "IN_1") (pintype "bidirectional"))
      (node (ref "USB") (pin "1") (pinfunction "VBUS_1") (pintype "bidirectional"))
    )
    (net (code "45") (name "/~{AVR_LED0}") (class "Default")
      (node (ref "AVR") (pin "C") (pinfunction "C_C") (pintype "passive"))
    )
    (net (code "46") (name "/~{AVR_LED1}") (class "Default")
      (node (ref "AVR1") (pin "C") (pinfunction "C_C") (pintype "passive"))
    )
    (net (code "47") (name "/~{CAS}") (class "Default")
      (node (ref "U10") (pin "71") (pinfunction "PX41_71") (pintype "bidirectional"))
      (node (ref "U13") (pin "17") (pinfunction "~{CAS}_17") (pintype "bidirectional"))
    )
    (net (code "48") (name "/~{CHANGE}") (class "Default")
      (node (ref "TO_AUX2") (pin "9") (pinfunction "9_9") (pintype "bidirectional"))
      (node (ref "U10") (pin "119") (pinfunction "PA25_119") (pintype "bidirectional"))
    )
    (net (code "49") (name "/~{CS_CC8530}") (class "Default")
      (node (ref "CC_DEBUG") (pin "5") (pinfunction "5_5") (pintype "bidirectional"))
      (node (ref "U10") (pin "133") (pinfunction "PA07_133") (pintype "bidirectional"))
      (node (ref "U2") (pin "3") (pinfunction "~{CS}_3") (pintype "bidirectional"))
    )
    (net (code "50") (name "/~{CS_CLOCK}") (class "Default")
      (node (ref "U10") (pin "129") (pinfunction "PA13_129") (pintype "bidirectional"))
      (node (ref "U9") (pin "8") (pinfunction "AD0/~{CS}_8") (pintype "bidirectional"))
    )
    (net (code "51") (name "/~{CS_CODEC}") (class "Default")
      (node (ref "U10") (pin "115") (pinfunction "PA18_115") (pintype "bidirectional"))
      (node (ref "U3") (pin "11") (pinfunction "AD0/~{CS}_11") (pintype "bidirectional"))
    )
    (net (code "52") (name "/~{CS_SDRAM}") (class "Default")
      (node (ref "U10") (pin "68") (pinfunction "PX14_68") (pintype "bidirectional"))
      (node (ref "U13") (pin "19") (pinfunction "~{CS}_19") (pintype "bidirectional"))
    )
    (net (code "53") (name "/~{CS_TOUCH}") (class "Default")
      (node (ref "TO_AUX2") (pin "7") (pinfunction "7_7") (pintype "bidirectional"))
      (node (ref "U10") (pin "116") (pinfunction "PA17_116") (pintype "bidirectional"))
    )
    (net (code "54") (name "/~{GPIO}") (class "Default")
      (node (ref "GPIO") (pin "2") (pinfunction "2_2") (pintype "bidirectional"))
      (node (ref "U10") (pin "73") (pinfunction "PX20_73") (pintype "bidirectional"))
    )
    (net (code "55") (name "/~{MUTE}") (class "Default")
      (node (ref "U10") (pin "113") (pinfunction "PA20_113") (pintype "bidirectional"))
      (node (ref "U3") (pin "21") (pinfunction "~{MUTEA}_21") (pintype "bidirectional"))
      (node (ref "U3") (pin "24") (pinfunction "~{MUTEB}_24") (pintype "bidirectional"))
    )
    (net (code "56") (name "/~{PAIR}") (class "Default")
      (node (ref "U10") (pin "127") (pinfunction "PA06_127") (pintype "bidirectional"))
      (node (ref "U2") (pin "7") (pinfunction "GIO1_7") (pintype "bidirectional"))
    )
    (net (code "57") (name "/~{RAS}") (class "Default")
      (node (ref "U10") (pin "69") (pinfunction "PX42_69") (pintype "bidirectional"))
      (node (ref "U13") (pin "18") (pinfunction "~{RAS}_18") (pintype "bidirectional"))
    )
    (net (code "58") (name "/~{RESET_CC8530}") (class "Default")
      (node (ref "CC_DEBUG") (pin "7") (pinfunction "7_7") (pintype "bidirectional"))
      (node (ref "L7") (pin "2") (pinfunction "2_2") (pintype "passive"))
    )
    (net (code "59") (name "/~{RESET_CODEC}") (class "Default")
      (node (ref "U10") (pin "122") (pinfunction "PA00_122") (pintype "bidirectional"))
      (node (ref "U3") (pin "14") (pinfunction "~{RESET}_14") (pintype "bidirectional"))
    )
    (net (code "60") (name "/~{RESET}") (class "Default")
      (node (ref "C73") (pin "1") (pinfunction "1_1") (pintype "passive"))
      (node (ref "JTAG") (pin "6") (pinfunction "6_6") (pintype "bidirectional"))
      (node (ref "R18") (pin "1") (pinfunction "1_1") (pintype "passive"))
      (node (ref "RESET") (pin "1") (pinfunction "1_1") (pintype "bidirectional"))
      (node (ref "U10") (pin "106") (pinfunction "~{RESET}_106") (pintype "bidirectional"))
    )
    (net (code "61") (name "/~{SD_CARD}") (class "Default")
      (node (ref "SD1") (pin "SWA") (pinfunction "SWA_SWA") (pintype "bidirectional"))
      (node (ref "U10") (pin "27") (pinfunction "PB01_27") (pintype "bidirectional"))
    )
    (net (code "62") (name "/~{WE_SDRAM}") (class "Default")
      (node (ref "U10") (pin "66") (pinfunction "PX44_66") (pintype "bidirectional"))
      (node (ref "U13") (pin "16") (pinfunction "~{WE}_16") (pintype "bidirectional"))
    )
    (net (code "63") (name "12MHZ") (class "Default")
      (node (ref "U10") (pin "18") (pinfunction "PC02_18") (pintype "bidirectional"))
      (node (ref "U9") (pin "5") (pinfunction "CLK_IN_5") (pintype "bidirectional"))
      (node (ref "X2") (pin "3") (pinfunction "OUT_3") (pintype "bidirectional"))
    )
    (net (code "64") (name "A3.3V") (class "Default")
      (node (ref "C39") (pin "1") (pinfunction "1_1") (pintype "passive"))
      (node (ref "C70") (pin "1") (pinfunction "1_1") (pintype "passive"))
      (node (ref "L15") (pin "2") (pinfunction "2_2") (pintype "passive"))
      (node (ref "L20") (pin "2") (pinfunction "2_2") (pintype "passive"))
      (node (ref "R13") (pin "2") (pinfunction "2_2") (pintype "passive"))
      (node (ref "R16") (pin "2") (pinfunction "2_2") (pintype "passive"))
      (node (ref "U4") (pin "6") (pinfunction "VDD_6") (pintype "bidirectional"))
      (node (ref "U7") (pin "5") (pinfunction "VOUT_5") (pintype "bidirectional"))
    )
    (net (code "65") (name "A10") (class "Default")
      (node (ref "U10") (pin "88") (pinfunction "PX43_88") (pintype "bidirectional"))
      (node (ref "U13") (pin "22") (pinfunction "A10/AP_22") (pintype "bidirectional"))
    )
    (net (code "66") (name "AGND") (class "Default")
      (node (ref "C30") (pin "2") (pinfunction "2_2") (pintype "passive"))
      (node (ref "C31") (pin "2") (pinfunction "2_2") (pintype "passive"))
      (node (ref "C39") (pin "2") (pinfunction "2_2") (pintype "passive"))
      (node (ref "C44") (pin "2") (pinfunction "2_2") (pintype "passive"))
      (node (ref "C45") (pin "2") (pinfunction "2_2") (pintype "passive"))
      (node (ref "C46") (pin "2") (pinfunction "2_2") (pintype "passive"))
      (node (ref "C47") (pin "2") (pinfunction "2_2") (pintype "passive"))
      (node (ref "C63") (pin "2") (pinfunction "2_2") (pintype "passive"))
      (node (ref "C64") (pin "2") (pinfunction "2_2") (pintype "passive"))
      (node (ref "C65") (pin "2") (pinfunction "2_2") (pintype "passive"))
      (node (ref "C70") (pin "2") (pinfunction "2_2") (pintype "passive"))
      (node (ref "C71") (pin "2") (pinfunction "2_2") (pintype "passive"))
      (node (ref "C98") (pin "2") (pinfunction "2_2") (pintype "passive"))
      (node (ref "C99") (pin "2") (pinfunction "2_2") (pintype "passive"))
      (node (ref "LINE_IN") (pin "5") (pinfunction "GND_5") (pintype "bidirectional"))
      (node (ref "PHONE_OUT") (pin "5") (pinfunction "GND_5") (pintype "bidirectional"))
      (node (ref "R19") (pin "1") (pinfunction "1_1") (pintype "passive"))
      (node (ref "R24") (pin "2") (pinfunction "2_2") (pintype "passive"))
      (node (ref "R25") (pin "1") (pinfunction "1_1") (pintype "passive"))
      (node (ref "U10") (pin "117") (pinfunction "GNDANA_117") (pintype "bidirectional"))
      (node (ref "U3") (pin "20") (pinfunction "AGND_20") (pintype "bidirectional"))
      (node (ref "U4") (pin "2") (pinfunction "VSS_2") (pintype "bidirectional"))
      (node (ref "U7") (pin "2") (pinfunction "GND_2") (pintype "bidirectional"))
    )
    (net (code "67") (name "AUDIO") (class "Default")
      (node (ref "C53") (pin "1") (pinfunction "1_1") (pintype "passive"))
      (node (ref "R7") (pin "1") (pinfunction "1_1") (pintype "passive"))
      (node (ref "U10") (pin "112") (pinfunction "PA24_112") (pintype "bidirectional"))
      (node (ref "U4") (pin "7") (pinfunction "OUTA_7") (pintype "bidirectional"))
    )
    (net (code "68") (name "AUX_BLUE") (class "Default")
      (node (ref "R42") (pin "1") (pinfunction "1_1") (pintype "passive"))
      (node (ref "TO_MAIN2") (pin "4") (pinfunction "4_4") (pintype "bidirectional"))
    )
    (net (code "69") (name "AUX_CS") (class "Default")
      (node (ref "TO_MAIN1") (pin "8") (pinfunction "8_8") (pintype "bidirectional"))
      (node (ref "U11") (pin "14") (pinfunction "~{SS}_14") (pintype "bidirectional"))
    )
    (net (code "70") (name "AUX_GREEN") (class "Default")
      (node (ref "R23") (pin "1") (pinfunction "1_1") (pintype "passive"))
      (node (ref "TO_MAIN2") (pin "6") (pinfunction "6_6") (pintype "bidirectional"))
    )
    (net (code "71") (name "AUX_MISO") (class "Default")
      (node (ref "TO_MAIN1") (pin "4") (pinfunction "4_4") (pintype "bidirectional"))
      (node (ref "U11") (pin "16") (pinfunction "MISO_16") (pintype "bidirectional"))
    )
    (net (code "72") (name "AUX_MOSI") (class "Default")
      (node (ref "TO_MAIN1") (pin "6") (pinfunction "6_6") (pintype "bidirectional"))
      (node (ref "U11") (pin "15") (pinfunction "MOSI_15") (pintype "bidirectional"))
    )
    (net (code "73") (name "AUX_RED") (class "Default")
      (node (ref "R10") (pin "1") (pinfunction "1_1") (pintype "passive"))
      (node (ref "TO_MAIN2") (pin "8") (pinfunction "8_8") (pintype "bidirectional"))
    )
    (net (code "74") (name "AUX_SCLK") (class "Default")
      (node (ref "TO_MAIN1") (pin "2") (pinfunction "2_2") (pintype "bidirectional"))
      (node (ref "U11") (pin "17") (pinfunction "SCK_17") (pintype "bidirectional"))
    )
    (net (code "75") (name "BA0") (class "Default")
      (node (ref "U10") (pin "84") (pinfunction "PX18_84") (pintype "bidirectional"))
      (node (ref "U13") (pin "20") (pinfunction "BA0_20") (pintype "bidirectional"))
    )
    (net (code "76") (name "BA1") (class "Default")
      (node (ref "U10") (pin "83") (pinfunction "PX17_83") (pintype "bidirectional"))
      (node (ref "U13") (pin "21") (pinfunction "BA1_21") (pintype "bidirectional"))
    )
    (net (code "77") (name "BAT") (class "Default")
      (node (ref "BATTERY") (pin "+") (pinfunction "P_+") (pintype "passive"))
      (node (ref "C60") (pin "1") (pinfunction "1_1") (pintype "passive"))
      (node (ref "F1") (pin "1") (pinfunction "1_1") (pintype "passive"))
      (node (ref "R11") (pin "2") (pinfunction "2_2") (pintype "passive"))
      (node (ref "U2") (pin "29") (pinfunction "VBAT_29") (pintype "bidirectional"))
      (node (ref "U6") (pin "10") (pinfunction "OUT_10") (pintype "bidirectional"))
    )
    (net (code "78") (name "BCLK") (class "Default")
      (node (ref "L9") (pin "1") (pinfunction "1_1") (pintype "passive"))
      (node (ref "U10") (pin "135") (pinfunction "PB07_135") (pintype "bidirectional"))
      (node (ref "U3") (pin "4") (pinfunction "BCLK_4") (pintype "bidirectional"))
    )
    (net (code "79") (name "BLUE") (class "Default")
      (node (ref "TO_AUX1") (pin "7") (pinfunction "7_7") (pintype "bidirectional"))
      (node (ref "U10") (pin "139") (pinfunction "PA09_139") (pintype "bidirectional"))
    )
    (net (code "80") (name "BLUE_TOP") (class "Default")
      (node (ref "U10") (pin "35") (pinfunction "PX19_35") (pintype "bidirectional"))
    )
    (net (code "81") (name "CKE") (class "Default")
      (node (ref "U10") (pin "74") (pinfunction "PX46_74") (pintype "bidirectional"))
      (node (ref "U13") (pin "37") (pinfunction "CKE_37") (pintype "bidirectional"))
    )
    (net (code "82") (name "CLK") (class "Default")
      (node (ref "U10") (pin "70") (pinfunction "PX45_70") (pintype "bidirectional"))
      (node (ref "U13") (pin "38") (pinfunction "CLK_38") (pintype "bidirectional"))
    )
    (net (code "83") (name "D+_UC") (class "Default")
      (node (ref "R15") (pin "2") (pinfunction "2_2") (pintype "passive"))
      (node (ref "U10") (pin "6") (pinfunction "D+_HS_6") (pintype "bidirectional"))
      (node (ref "USB") (pin "3") (pinfunction "D+_3") (pintype "bidirectional"))
    )
    (net (code "84") (name "D-_UC") (class "Default")
      (node (ref "R17") (pin "2") (pinfunction "2_2") (pintype "passive"))
      (node (ref "U10") (pin "5") (pinfunction "D-_HS_5") (pintype "bidirectional"))
      (node (ref "USB") (pin "2") (pinfunction "D-_2") (pintype "bidirectional"))
    )
    (net (code "85") (name "D3.3V") (class "Default")
      (node (ref "C100") (pin "1") (pinfunction "1_1") (pintype "passive"))
      (node (ref "C101") (pin "1") (pinfunction "1_1") (pintype "passive"))
      (node (ref "C102") (pin "1") (pinfunction "1_1") (pintype "passive"))
      (node (ref "C103") (pin "1") (pinfunction "1_1") (pintype "passive"))
      (node (ref "C26") (pin "1") (pinfunction "1_1") (pintype "passive"))
      (node (ref "C28") (pin "1") (pinfunction "1_1") (pintype "passive"))
      (node (ref "C29") (pin "1") (pinfunction "1_1") (pintype "passive"))
      (node (ref "C32") (pin "1") (pinfunction "1_1") (pintype "passive"))
      (node (ref "C33") (pin "1") (pinfunction "1_1") (pintype "passive"))
      (node (ref "C34") (pin "1") (pinfunction "1_1") (pintype "passive"))
      (node (ref "C35") (pin "1") (pinfunction "1_1") (pintype "passive"))
      (node (ref "C40") (pin "1") (pinfunction "1_1") (pintype "passive"))
      (node (ref "C41") (pin "1") (pinfunction "1_1") (pintype "passive"))
      (node (ref "C42") (pin "1") (pinfunction "1_1") (pintype "passive"))
      (node (ref "C43") (pin "1") (pinfunction "1_1") (pintype "passive"))
      (node (ref "C48") (pin "1") (pinfunction "1_1") (pintype "passive"))
      (node (ref "C49") (pin "1") (pinfunction "1_1") (pintype "passive"))
      (node (ref "C50") (pin "1") (pinfunction "1_1") (pintype "passive"))
      (node (ref "C51") (pin "1") (pinfunction "1_1") (pintype "passive"))
      (node (ref "C55") (pin "1") (pinfunction "1_1") (pintype "passive"))
      (node (ref "C56") (pin "1") (pinfunction "1_1") (pintype "passive"))
      (node (ref "C57") (pin "1") (pinfunction "1_1") (pintype "passive"))
      (node (ref "C58") (pin "1") (pinfunction "1_1") (pintype "passive"))
      (node (ref "C61") (pin "1") (pinfunction "1_1") (pintype "passive"))
      (node (ref "C72") (pin "1") (pinfunction "1_1") (pintype "passive"))
      (node (ref "C74") (pin "1") (pinfunction "1_1") (pintype "passive"))
      (node (ref "C75") (pin "1") (pinfunction "1_1") (pintype "passive"))
      (node (ref "C77") (pin "1") (pinfunction "1_1") (pintype "passive"))
      (node (ref "C78") (pin "1") (pinfunction "1_1") (pintype "passive"))
      (node (ref "C79") (pin "1") (pinfunction "1_1") (pintype "passive"))
      (node (ref "C80") (pin "1") (pinfunction "1_1") (pintype "passive"))
      (node (ref "C81") (pin "1") (pinfunction "1_1") (pintype "passive"))
      (node (ref "C83") (pin "1") (pinfunction "1_1") (pintype "passive"))
      (node (ref "C84") (pin "1") (pinfunction "1_1") (pintype "passive"))
      (node (ref "C95") (pin "1") (pinfunction "1_1") (pintype "passive"))
      (node (ref "C96") (pin "1") (pinfunction "1_1") (pintype "passive"))
      (node (ref "C97") (pin "1") (pinfunction "1_1") (pintype "passive"))
      (node (ref "CC_DEBUG") (pin "2") (pinfunction "2_2") (pintype "bidirectional"))
      (node (ref "JTAG") (pin "4") (pinfunction "4_4") (pintype "bidirectional"))
      (node (ref "L1") (pin "2") (pinfunction "2_2") (pintype "passive"))
      (node (ref "L17") (pin "2") (pinfunction "2_2") (pintype "passive"))
      (node (ref "L19") (pin "2") (pinfunction "2_2") (pintype "passive"))
      (node (ref "L2") (pin "2") (pinfunction "2_2") (pintype "passive"))
      (node (ref "L3") (pin "2") (pinfunction "2_2") (pintype "passive"))
      (node (ref "R12") (pin "2") (pinfunction "2_2") (pintype "passive"))
      (node (ref "R18") (pin "2") (pinfunction "2_2") (pintype "passive"))
      (node (ref "R20") (pin "2") (pinfunction "2_2") (pintype "passive"))
      (node (ref "R22") (pin "2") (pinfunction "2_2") (pintype "passive"))
      (node (ref "R5") (pin "2") (pinfunction "2_2") (pintype "passive"))
      (node (ref "R8") (pin "2") (pinfunction "2_2") (pintype "passive"))
      (node (ref "SD1") (pin "VDD") (pinfunction "VDD_VDD") (pintype "bidirectional"))
      (node (ref "U10") (pin "10") (pinfunction "VDDIO_10") (pintype "bidirectional"))
      (node (ref "U10") (pin "103") (pinfunction "VDDIO_103") (pintype "bidirectional"))
      (node (ref "U10") (pin "130") (pinfunction "VDDIO_130") (pintype "bidirectional"))
      (node (ref "U10") (pin "142") (pinfunction "VDDIN_142") (pintype "bidirectional"))
      (node (ref "U10") (pin "143") (pinfunction "VDDIN_143") (pintype "bidirectional"))
      (node (ref "U10") (pin "2") (pinfunction "VDDIO_2") (pintype "bidirectional"))
      (node (ref "U10") (pin "21") (pinfunction "VDDIO_21") (pintype "bidirectional"))
      (node (ref "U10") (pin "48") (pinfunction "VDDIO_48") (pintype "bidirectional"))
      (node (ref "U10") (pin "64") (pinfunction "VDDIO_64") (pintype "bidirectional"))
      (node (ref "U10") (pin "81") (pinfunction "VDDIO_81") (pintype "bidirectional"))
      (node (ref "U13") (pin "1") (pinfunction "VDD_1") (pintype "bidirectional"))
      (node (ref "U13") (pin "14") (pinfunction "VDD_14") (pintype "bidirectional"))
      (node (ref "U13") (pin "27") (pinfunction "VDD_27") (pintype "bidirectional"))
      (node (ref "U13") (pin "3") (pinfunction "VDDQ_3") (pintype "bidirectional"))
      (node (ref "U13") (pin "43") (pinfunction "VDDQ_43") (pintype "bidirectional"))
      (node (ref "U13") (pin "49") (pinfunction "VDDQ_49") (pintype "bidirectional"))
      (node (ref "U13") (pin "9") (pinfunction "VDDQ_9") (pintype "bidirectional"))
      (node (ref "U3") (pin "5") (pinfunction "VD_5") (pintype "bidirectional"))
      (node (ref "U3") (pin "8") (pinfunction "VLC_8") (pintype "bidirectional"))
      (node (ref "U5") (pin "3") (pinfunction "VOUT_3") (pintype "bidirectional"))
      (node (ref "U8") (pin "5") (pinfunction "VCC_5") (pintype "bidirectional"))
      (node (ref "U9") (pin "1") (pinfunction "VD_1") (pintype "bidirectional"))
      (node (ref "X2") (pin "4") (pinfunction "VDD_4") (pintype "bidirectional"))
      (node (ref "X3") (pin "4") (pinfunction "VDD_4") (pintype "bidirectional"))
    )
    (net (code "86") (name "DGND") (class "Default")
      (node (ref "C1") (pin "2") (pinfunction "2_2") (pintype "passive"))
      (node (ref "C10") (pin "2") (pinfunction "2_2") (pintype "passive"))
      (node (ref "C100") (pin "2") (pinfunction "2_2") (pintype "passive"))
      (node (ref "C101") (pin "2") (pinfunction "2_2") (pintype "passive"))
      (node (ref "C102") (pin "2") (pinfunction "2_2") (pintype "passive"))
      (node (ref "C103") (pin "2") (pinfunction "2_2") (pintype "passive"))
      (node (ref "C11") (pin "2") (pinfunction "2_2") (pintype "passive"))
      (node (ref "C12") (pin "2") (pinfunction "2_2") (pintype "passive"))
      (node (ref "C13") (pin "2") (pinfunction "2_2") (pintype "passive"))
      (node (ref "C14") (pin "2") (pinfunction "2_2") (pintype "passive"))
      (node (ref "C15") (pin "2") (pinfunction "2_2") (pintype "passive"))
      (node (ref "C16") (pin "2") (pinfunction "2_2") (pintype "passive"))
      (node (ref "C17") (pin "2") (pinfunction "2_2") (pintype "passive"))
      (node (ref "C18") (pin "2") (pinfunction "2_2") (pintype "passive"))
      (node (ref "C19") (pin "2") (pinfunction "2_2") (pintype "passive"))
      (node (ref "C2") (pin "2") (pinfunction "2_2") (pintype "passive"))
      (node (ref "C20") (pin "2") (pinfunction "2_2") (pintype "passive"))
      (node (ref "C23") (pin "2") (pinfunction "2_2") (pintype "passive"))
      (node (ref "C24") (pin "2") (pinfunction "2_2") (pintype "passive"))
      (node (ref "C25") (pin "2") (pinfunction "2_2") (pintype "passive"))
      (node (ref "C26") (pin "2") (pinfunction "2_2") (pintype "passive"))
      (node (ref "C28") (pin "2") (pinfunction "2_2") (pintype "passive"))
      (node (ref "C29") (pin "2") (pinfunction "2_2") (pintype "passive"))
      (node (ref "C3") (pin "2") (pinfunction "2_2") (pintype "passive"))
      (node (ref "C32") (pin "2") (pinfunction "2_2") (pintype "passive"))
      (node (ref "C33") (pin "2") (pinfunction "2_2") (pintype "passive"))
      (node (ref "C34") (pin "2") (pinfunction "2_2") (pintype "passive"))
      (node (ref "C35") (pin "2") (pinfunction "2_2") (pintype "passive"))
      (node (ref "C4") (pin "2") (pinfunction "2_2") (pintype "passive"))
      (node (ref "C40") (pin "2") (pinfunction "2_2") (pintype "passive"))
      (node (ref "C41") (pin "2") (pinfunction "2_2") (pintype "passive"))
      (node (ref "C42") (pin "2") (pinfunction "2_2") (pintype "passive"))
      (node (ref "C43") (pin "2") (pinfunction "2_2") (pintype "passive"))
      (node (ref "C48") (pin "2") (pinfunction "2_2") (pintype "passive"))
      (node (ref "C49") (pin "2") (pinfunction "2_2") (pintype "passive"))
      (node (ref "C5") (pin "2") (pinfunction "2_2") (pintype "passive"))
      (node (ref "C50") (pin "2") (pinfunction "2_2") (pintype "passive"))
      (node (ref "C51") (pin "2") (pinfunction "2_2") (pintype "passive"))
      (node (ref "C54") (pin "2") (pinfunction "2_2") (pintype "passive"))
      (node (ref "C55") (pin "2") (pinfunction "2_2") (pintype "passive"))
      (node (ref "C56") (pin "2") (pinfunction "2_2") (pintype "passive"))
      (node (ref "C57") (pin "2") (pinfunction "2_2") (pintype "passive"))
      (node (ref "C58") (pin "2") (pinfunction "2_2") (pintype "passive"))
      (node (ref "C6") (pin "2") (pinfunction "2_2") (pintype "passive"))
      (node (ref "C61") (pin "2") (pinfunction "2_2") (pintype "passive"))
      (node (ref "C62") (pin "2") (pinfunction "2_2") (pintype "passive"))
      (node (ref "C68") (pin "2") (pinfunction "2_2") (pintype "passive"))
      (node (ref "C69") (pin "2") (pinfunction "2_2") (pintype "passive"))
      (node (ref "C7") (pin "2") (pinfunction "2_2") (pintype "passive"))
      (node (ref "C72") (pin "2") (pinfunction "2_2") (pintype "passive"))
      (node (ref "C73") (pin "2") (pinfunction "2_2") (pintype "passive"))
      (node (ref "C74") (pin "2") (pinfunction "2_2") (pintype "passive"))
      (node (ref "C75") (pin "2") (pinfunction "2_2") (pintype "passive"))
      (node (ref "C76") (pin "2") (pinfunction "2_2") (pintype "passive"))
      (node (ref "C77") (pin "2") (pinfunction "2_2") (pintype "passive"))
      (node (ref "C78") (pin "2") (pinfunction "2_2") (pintype "passive"))
      (node (ref "C79") (pin "2") (pinfunction "2_2") (pintype "passive"))
      (node (ref "C8") (pin "2") (pinfunction "2_2") (pintype "passive"))
      (node (ref "C80") (pin "2") (pinfunction "2_2") (pintype "passive"))
      (node (ref "C81") (pin "2") (pinfunction "2_2") (pintype "passive"))
      (node (ref "C82") (pin "2") (pinfunction "2_2") (pintype "passive"))
      (node (ref "C83") (pin "2") (pinfunction "2_2") (pintype "passive"))
      (node (ref "C84") (pin "2") (pinfunction "2_2") (pintype "passive"))
      (node (ref "C9") (pin "2") (pinfunction "2_2") (pintype "passive"))
      (node (ref "C95") (pin "2") (pinfunction "2_2") (pintype "passive"))
      (node (ref "C96") (pin "2") (pinfunction "2_2") (pintype "passive"))
      (node (ref "C97") (pin "2") (pinfunction "2_2") (pintype "passive"))
      (node (ref "CC_DEBUG") (pin "1") (pinfunction "1_1") (pintype "bidirectional"))
      (node (ref "GPIO") (pin "4") (pinfunction "4_4") (pintype "bidirectional"))
      (node (ref "JTAG") (pin "10") (pinfunction "10_10") (pintype "bidirectional"))
      (node (ref "JTAG") (pin "2") (pinfunction "2_2") (pintype "bidirectional"))
      (node (ref "L6") (pin "1") (pinfunction "1_1") (pintype "passive"))
      (node (ref "POWER") (pin "C") (pinfunction "C_C") (pintype "passive"))
      (node (ref "R2") (pin "1") (pinfunction "1_1") (pintype "passive"))
      (node (ref "R26") (pin "2") (pinfunction "2_2") (pintype "passive"))
      (node (ref "R27") (pin "1") (pinfunction "1_1") (pintype "passive"))
      (node (ref "R3") (pin "1") (pinfunction "1_1") (pintype "passive"))
      (node (ref "R6") (pin "1") (pinfunction "1_1") (pintype "passive"))
      (node (ref "RESET") (pin "3") (pinfunction "3_3") (pintype "bidirectional"))
      (node (ref "SD1") (pin "GND1") (pinfunction "GND_GND1") (pintype "bidirectional"))
      (node (ref "SD1") (pin "GND2") (pinfunction "GND_GND2") (pintype "bidirectional"))
      (node (ref "SD1") (pin "GND3") (pinfunction "GND_GND3") (pintype "bidirectional"))
      (node (ref "SD1") (pin "GND4") (pinfunction "GND_GND4") (pintype "bidirectional"))
      (node (ref "SD1") (pin "SWB") (pinfunction "SWB_SWB") (pintype "bidirectional"))
      (node (ref "SD1") (pin "VSS") (pinfunction "GND_VSS") (pintype "bidirectional"))
      (node (ref "SERIAL") (pin "6") (pinfunction "6_6") (pintype "bidirectional"))
      (node (ref "SMA") (pin "GND1") (pinfunction "GND_GND1") (pintype "bidirectional"))
      (node (ref "SMA") (pin "GND2") (pinfunction "GND_GND2") (pintype "bidirectional"))
      (node (ref "SMA") (pin "GND3") (pinfunction "GND_GND3") (pintype "bidirectional"))
      (node (ref "SMA") (pin "GND4") (pinfunction "GND_GND4") (pintype "bidirectional"))
      (node (ref "TO_AUX1") (pin "10") (pinfunction "10_10") (pintype "bidirectional"))
      (node (ref "TO_AUX1") (pin "4") (pinfunction "4_4") (pintype "bidirectional"))
      (node (ref "TO_AUX1") (pin "6") (pinfunction "6_6") (pintype "bidirectional"))
      (node (ref "TO_AUX1") (pin "8") (pinfunction "8_8") (pintype "bidirectional"))
      (node (ref "TO_AUX1") (pin "9") (pinfunction "9_9") (pintype "bidirectional"))
      (node (ref "TO_AUX2") (pin "10") (pinfunction "10_10") (pintype "bidirectional"))
      (node (ref "TO_AUX2") (pin "6") (pinfunction "6_6") (pintype "bidirectional"))
      (node (ref "TO_AUX2") (pin "8") (pinfunction "8_8") (pintype "bidirectional"))
      (node (ref "U1") (pin "12") (pinfunction "GND_12") (pintype "bidirectional"))
      (node (ref "U1") (pin "14") (pinfunction "GND_14") (pintype "bidirectional"))
      (node (ref "U1") (pin "8") (pinfunction "GND_8") (pintype "bidirectional"))
      (node (ref "U1") (pin "9") (pinfunction "GND_9") (pintype "bidirectional"))
      (node (ref "U1") (pin "GND") (pinfunction "GND_GND") (pintype "bidirectional"))
      (node (ref "U10") (pin "102") (pinfunction "GNDIO_102") (pintype "bidirectional"))
      (node (ref "U10") (pin "131") (pinfunction "GNDIO_131") (pintype "bidirectional"))
      (node (ref "U10") (pin "140") (pinfunction "GNDCORE_140") (pintype "bidirectional"))
      (node (ref "U10") (pin "144") (pinfunction "GNDPLL_144") (pintype "bidirectional"))
      (node (ref "U10") (pin "20") (pinfunction "GNDIO_20") (pintype "bidirectional"))
      (node (ref "U10") (pin "4") (pinfunction "GNDIO_4") (pintype "bidirectional"))
      (node (ref "U10") (pin "47") (pinfunction "GNDIO_47") (pintype "bidirectional"))
      (node (ref "U10") (pin "65") (pinfunction "GNDIO_65") (pintype "bidirectional"))
      (node (ref "U10") (pin "7") (pinfunction "GNDIO_7") (pintype "bidirectional"))
      (node (ref "U10") (pin "82") (pinfunction "GNDIO_82") (pintype "bidirectional"))
      (node (ref "U13") (pin "12") (pinfunction "VSSQ_12") (pintype "bidirectional"))
      (node (ref "U13") (pin "28") (pinfunction "VSS_28") (pintype "bidirectional"))
      (node (ref "U13") (pin "41") (pinfunction "VSS_41") (pintype "bidirectional"))
      (node (ref "U13") (pin "46") (pinfunction "VSSQ_46") (pintype "bidirectional"))
      (node (ref "U13") (pin "52") (pinfunction "VSSQ_52") (pintype "bidirectional"))
      (node (ref "U13") (pin "54") (pinfunction "VSS_54") (pintype "bidirectional"))
      (node (ref "U13") (pin "6") (pinfunction "VSSQ_6") (pintype "bidirectional"))
      (node (ref "U2") (pin "19") (pinfunction "AD2/GIO9_19") (pintype "bidirectional"))
      (node (ref "U2") (pin "32") (pinfunction "SCL/GIO10_32") (pintype "bidirectional"))
      (node (ref "U2") (pin "33") (pinfunction "SDA/GIO11_33") (pintype "bidirectional"))
      (node (ref "U2") (pin "34") (pinfunction "GIO12_34") (pintype "bidirectional"))
      (node (ref "U2") (pin "35") (pinfunction "GIO13_35") (pintype "bidirectional"))
      (node (ref "U2") (pin "GND") (pinfunction "GND_GND") (pintype "bidirectional"))
      (node (ref "U3") (pin "6") (pinfunction "DGND_6") (pintype "bidirectional"))
      (node (ref "U5") (pin "2") (pinfunction "GND_2") (pintype "bidirectional"))
      (node (ref "U5") (pin "4") (pinfunction "GND_4") (pintype "bidirectional"))
      (node (ref "U8") (pin "3") (pinfunction "GND_3") (pintype "bidirectional"))
      (node (ref "U9") (pin "2") (pinfunction "GND_2") (pintype "bidirectional"))
      (node (ref "U9") (pin "7") (pinfunction "FILTN_7") (pintype "bidirectional"))
      (node (ref "X2") (pin "1") (pinfunction "~{EN}_1") (pintype "bidirectional"))
      (node (ref "X2") (pin "2") (pinfunction "VSS_2") (pintype "bidirectional"))
      (node (ref "X3") (pin "1") (pinfunction "~{EN}_1") (pintype "bidirectional"))
      (node (ref "X3") (pin "2") (pinfunction "VSS_2") (pintype "bidirectional"))
    )
    (net (code "87") (name "DIN") (class "Default")
      (node (ref "L13") (pin "1") (pinfunction "1_1") (pintype "passive"))
      (node (ref "U10") (pin "11") (pinfunction "PB08_11") (pintype "bidirectional"))
      (node (ref "U3") (pin "1") (pinfunction "DIN_1") (pintype "bidirectional"))
    )
    (net (code "88") (name "DOUT") (class "Default")
      (node (ref "L11") (pin "1") (pinfunction "1_1") (pintype "passive"))
      (node (ref "U10") (pin "17") (pinfunction "PB09_17") (pintype "bidirectional"))
      (node (ref "U3") (pin "7") (pinfunction "DOUT_7") (pintype "bidirectional"))
    )
    (net (code "89") (name "GREEN") (class "Default")
      (node (ref "TO_AUX1") (pin "5") (pinfunction "5_5") (pintype "bidirectional"))
      (node (ref "U10") (pin "134") (pinfunction "PB06_134") (pintype "bidirectional"))
    )
    (net (code "90") (name "IN_L") (class "Default")
      (node (ref "C38") (pin "1") (pinfunction "1_1") (pintype "passive"))
      (node (ref "LINE_IN") (pin "4") (pinfunction "L_4") (pintype "bidirectional"))
      (node (ref "R19") (pin "2") (pinfunction "2_2") (pintype "passive"))
    )
    (net (code "91") (name "IN_R") (class "Default")
      (node (ref "C36") (pin "1") (pinfunction "1_1") (pintype "passive"))
      (node (ref "LINE_IN") (pin "1") (pinfunction "R_1") (pintype "bidirectional"))
    )
    (net (code "92") (name "LDQM") (class "Default")
      (node (ref "U10") (pin "61") (pinfunction "PX34_61") (pintype "bidirectional"))
      (node (ref "U13") (pin "15") (pinfunction "LDQM_15") (pintype "bidirectional"))
    )
    (net (code "93") (name "LINEIN_SENSE") (class "Default")
      (node (ref "LINE_IN") (pin "3") (pinfunction "L_SW_3") (pintype "bidirectional"))
      (node (ref "R13") (pin "1") (pinfunction "1_1") (pintype "passive"))
      (node (ref "U10") (pin "109") (pinfunction "PA21_109") (pintype "bidirectional"))
    )
    (net (code "94") (name "LNA_EN") (class "Default")
      (node (ref "U1") (pin "6") (pinfunction "EN_6") (pintype "bidirectional"))
      (node (ref "U2") (pin "38") (pinfunction "XLNAEN_38") (pintype "bidirectional"))
    )
    (net (code "95") (name "MCI-CLK") (class "Default")
      (node (ref "SD1") (pin "CLK") (pinfunction "CLK/SCLK_CLK") (pintype "bidirectional"))
      (node (ref "U10") (pin "26") (pinfunction "PA27_26") (pintype "bidirectional"))
    )
    (net (code "96") (name "MCI-CMD") (class "Default")
      (node (ref "R22") (pin "1") (pinfunction "1_1") (pintype "passive"))
      (node (ref "SD1") (pin "CMD") (pinfunction "CMD/MOSI_CMD") (pintype "bidirectional"))
      (node (ref "U10") (pin "28") (pinfunction "PA28_28") (pintype "bidirectional"))
    )
    (net (code "97") (name "MCI-DATA0") (class "Default")
      (node (ref "R20") (pin "1") (pinfunction "1_1") (pintype "passive"))
      (node (ref "SD1") (pin "DAT0") (pinfunction "DAT0/MISO_DAT0") (pintype "bidirectional"))
      (node (ref "U10") (pin "23") (pinfunction "PA29_23") (pintype "bidirectional"))
    )
    (net (code "98") (name "MCI-DATA1") (class "Default")
      (node (ref "SD1") (pin "DAT1") (pinfunction "DAT1/NC_DAT1") (pintype "bidirectional"))
      (node (ref "U10") (pin "14") (pinfunction "PA30_14") (pintype "bidirectional"))
    )
    (net (code "99") (name "MCI-DATA2") (class "Default")
      (node (ref "SD1") (pin "DAT2") (pinfunction "DAT2/NC_DAT2") (pintype "bidirectional"))
      (node (ref "U10") (pin "29") (pinfunction "PA31_29") (pintype "bidirectional"))
    )
    (net (code "100") (name "MCI-DATA3") (class "Default")
      (node (ref "SD1") (pin "CD/DAT3") (pinfunction "CD/DAT3/~{CS}_CD/DAT3") (pintype "bidirectional"))
      (node (ref "U10") (pin "30") (pinfunction "PB00_30") (pintype "bidirectional"))
    )
    (net (code "101") (name "MCLK") (class "Default")
      (node (ref "U3") (pin "3") (pinfunction "MCLK_3") (pintype "bidirectional"))
      (node (ref "U8") (pin "2") (pinfunction "CLK_2") (pintype "bidirectional"))
      (node (ref "U9") (pin "3") (pinfunction "CLK_OUT_3") (pintype "bidirectional"))
    )
    (net (code "102") (name "MISO0") (class "Default")
      (node (ref "CC_DEBUG") (pin "10") (pinfunction "10_10") (pintype "bidirectional"))
      (node (ref "U10") (pin "136") (pinfunction "PA11_136") (pintype "bidirectional"))
      (node (ref "U2") (pin "6") (pinfunction "MISO_6") (pintype "bidirectional"))
    )
    (net (code "103") (name "MISO1") (class "Default")
      (node (ref "TO_AUX2") (pin "3") (pinfunction "3_3") (pintype "bidirectional"))
      (node (ref "U10") (pin "114") (pinfunction "PA19_114") (pintype "bidirectional"))
      (node (ref "U3") (pin "9") (pinfunction "SDA/MISO_9") (pintype "bidirectional"))
    )
    (net (code "104") (name "MOSI0") (class "Default")
      (node (ref "CC_DEBUG") (pin "8") (pinfunction "8_8") (pintype "bidirectional"))
      (node (ref "U10") (pin "138") (pinfunction "PA10_138") (pintype "bidirectional"))
      (node (ref "U2") (pin "5") (pinfunction "MOSI_5") (pintype "bidirectional"))
      (node (ref "U9") (pin "10") (pinfunction "SDA/MOSI_10") (pintype "bidirectional"))
    )
    (net (code "105") (name "MOSI1") (class "Default")
      (node (ref "TO_AUX2") (pin "5") (pinfunction "5_5") (pintype "bidirectional"))
      (node (ref "U10") (pin "128") (pinfunction "PA16_128") (pintype "bidirectional"))
      (node (ref "U3") (pin "12") (pinfunction "AD1/MOSI_12") (pintype "bidirectional"))
    )
    (net (code "106") (name "Net-(AVR-PadA)") (class "Default")
      (node (ref "AVR") (pin "A") (pinfunction "A_A") (pintype "passive"))
      (node (ref "R8") (pin "1") (pinfunction "1_1") (pintype "passive"))
    )
    (net (code "107") (name "Net-(AVR1-PadA)") (class "Default")
      (node (ref "AVR1") (pin "A") (pinfunction "A_A") (pintype "passive"))
      (node (ref "R5") (pin "1") (pinfunction "1_1") (pintype "passive"))
    )
    (net (code "108") (name "Net-(BUTTON-PadP$1)") (class "Default")
      (node (ref "BUTTON") (pin "P$1") (pinfunction "P$1_P$1") (pintype "bidirectional"))
      (node (ref "R31") (pin "2") (pinfunction "2_2") (pintype "passive"))
    )
    (net (code "109") (name "Net-(C21-Pad1)") (class "Default")
      (node (ref "C21") (pin "1") (pinfunction "1_1") (pintype "passive"))
      (node (ref "L5") (pin "2") (pinfunction "2_2") (pintype "passive"))
    )
    (net (code "110") (name "Net-(C21-Pad2)") (class "Default")
      (node (ref "C21") (pin "2") (pinfunction "2_2") (pintype "passive"))
      (node (ref "C22") (pin "1") (pinfunction "1_1") (pintype "passive"))
      (node (ref "C24") (pin "1") (pinfunction "1_1") (pintype "passive"))
      (node (ref "L6") (pin "2") (pinfunction "2_2") (pintype "passive"))
    )
    (net (code "111") (name "Net-(C22-Pad2)") (class "Default")
      (node (ref "C22") (pin "2") (pinfunction "2_2") (pintype "passive"))
      (node (ref "SMA") (pin "SIG") (pinfunction "SIG_SIG") (pintype "bidirectional"))
    )
    (net (code "112") (name "Net-(C23-Pad1)") (class "Default")
      (node (ref "C23") (pin "1") (pinfunction "1_1") (pintype "passive"))
      (node (ref "L4") (pin "2") (pinfunction "2_2") (pintype "passive"))
      (node (ref "L5") (pin "1") (pinfunction "1_1") (pintype "passive"))
    )
    (net (code "113") (name "Net-(C52-Pad1)") (class "Default")
      (node (ref "C52") (pin "1") (pinfunction "1_1") (pintype "passive"))
      (node (ref "R41") (pin "1") (pinfunction "1_1") (pintype "passive"))
    )
    (net (code "114") (name "Net-(C52-Pad2)") (class "Default")
      (node (ref "C52") (pin "2") (pinfunction "2_2") (pintype "passive"))
      (node (ref "C98") (pin "1") (pinfunction "1_1") (pintype "passive"))
      (node (ref "R9") (pin "2") (pinfunction "2_2") (pintype "passive"))
    )
    (net (code "115") (name "Net-(C54-Pad1)") (class "Default")
      (node (ref "C54") (pin "1") (pinfunction "1_1") (pintype "passive"))
      (node (ref "L17") (pin "1") (pinfunction "1_1") (pintype "passive"))
      (node (ref "TO_AUX1") (pin "1") (pinfunction "1_1") (pintype "bidirectional"))
      (node (ref "TO_AUX1") (pin "2") (pinfunction "2_2") (pintype "bidirectional"))
    )
    (net (code "116") (name "Net-(C62-Pad1)") (class "Default")
      (node (ref "C62") (pin "1") (pinfunction "1_1") (pintype "passive"))
      (node (ref "L19") (pin "1") (pinfunction "1_1") (pintype "passive"))
      (node (ref "TO_AUX2") (pin "2") (pinfunction "2_2") (pintype "bidirectional"))
      (node (ref "TO_AUX2") (pin "4") (pinfunction "4_4") (pintype "bidirectional"))
    )
    (net (code "117") (name "Net-(C67-Pad1)") (class "Default")
      (node (ref "C67") (pin "1") (pinfunction "1_1") (pintype "passive"))
      (node (ref "R40") (pin "1") (pinfunction "1_1") (pintype "passive"))
    )
    (net (code "118") (name "Net-(C67-Pad2)") (class "Default")
      (node (ref "C67") (pin "2") (pinfunction "2_2") (pintype "passive"))
      (node (ref "C99") (pin "1") (pinfunction "1_1") (pintype "passive"))
      (node (ref "R14") (pin "2") (pinfunction "2_2") (pintype "passive"))
    )
    (net (code "119") (name "Net-(CC1-PadC)") (class "Default")
      (node (ref "CC1") (pin "C") (pinfunction "C_C") (pintype "passive"))
      (node (ref "R4") (pin "2") (pinfunction "2_2") (pintype "passive"))
    )
    (net (code "120") (name "Net-(CHARGE-PadA)") (class "Default")
      (node (ref "CHARGE") (pin "A") (pinfunction "A_A") (pintype "passive"))
      (node (ref "R11") (pin "1") (pinfunction "1_1") (pintype "passive"))
    )
    (net (code "121") (name "Net-(NEXT-PadP$1)") (class "Default")
      (node (ref "NEXT") (pin "P$1") (pinfunction "P$1_P$1") (pintype "bidirectional"))
      (node (ref "R30") (pin "2") (pinfunction "2_2") (pintype "passive"))
    )
    (net (code "122") (name "Net-(PLAY/PAUSE-PadP$1)") (class "Default")
      (node (ref "PLAY/PAUSE") (pin "P$1") (pinfunction "P$1_P$1") (pintype "bidirectional"))
      (node (ref "R36") (pin "2") (pinfunction "2_2") (pintype "passive"))
    )
    (net (code "123") (name "Net-(POWER-PadA)") (class "Default")
      (node (ref "POWER") (pin "A") (pinfunction "A_A") (pintype "passive"))
      (node (ref "R12") (pin "1") (pinfunction "1_1") (pintype "passive"))
    )
    (net (code "124") (name "Net-(PREV-PadP$1)") (class "Default")
      (node (ref "PREV") (pin "P$1") (pinfunction "P$1_P$1") (pintype "bidirectional"))
      (node (ref "R35") (pin "2") (pinfunction "2_2") (pintype "passive"))
    )
    (net (code "125") (name "Net-(Q2-D)") (class "Default")
      (node (ref "LED_LL") (pin "1") (pinfunction "KR_1") (pintype "passive"))
      (node (ref "LED_LL") (pin "1-2") (pinfunction "KR_1-2") (pintype "passive"))
      (node (ref "LED_LR") (pin "1") (pinfunction "KR_1") (pintype "passive"))
      (node (ref "LED_LR") (pin "1-2") (pinfunction "KR_1-2") (pintype "passive"))
      (node (ref "LED_UL") (pin "1") (pinfunction "KR_1") (pintype "passive"))
      (node (ref "LED_UL") (pin "1-2") (pinfunction "KR_1-2") (pintype "passive"))
      (node (ref "LED_UR") (pin "1") (pinfunction "KR_1") (pintype "passive"))
      (node (ref "LED_UR") (pin "1-2") (pinfunction "KR_1-2") (pintype "passive"))
      (node (ref "Q2") (pin "3") (pinfunction "D_3") (pintype "passive"))
    )
    (net (code "126") (name "Net-(Q2-G)") (class "Default")
      (node (ref "Q2") (pin "1") (pinfunction "G_1") (pintype "passive"))
      (node (ref "R10") (pin "2") (pinfunction "2_2") (pintype "passive"))
    )
    (net (code "127") (name "Net-(Q4-D)") (class "Default")
      (node (ref "LED_LL") (pin "4") (pinfunction "KG_4") (pintype "passive"))
      (node (ref "LED_LL") (pin "4-2") (pinfunction "KG_4-2") (pintype "passive"))
      (node (ref "LED_LR") (pin "4") (pinfunction "KG_4") (pintype "passive"))
      (node (ref "LED_LR") (pin "4-2") (pinfunction "KG_4-2") (pintype "passive"))
      (node (ref "LED_UL") (pin "4") (pinfunction "KG_4") (pintype "passive"))
      (node (ref "LED_UL") (pin "4-2") (pinfunction "KG_4-2") (pintype "passive"))
      (node (ref "LED_UR") (pin "4") (pinfunction "KG_4") (pintype "passive"))
      (node (ref "LED_UR") (pin "4-2") (pinfunction "KG_4-2") (pintype "passive"))
      (node (ref "Q4") (pin "3") (pinfunction "D_3") (pintype "passive"))
    )
    (net (code "128") (name "Net-(Q4-G)") (class "Default")
      (node (ref "Q4") (pin "1") (pinfunction "G_1") (pintype "passive"))
      (node (ref "R23") (pin "2") (pinfunction "2_2") (pintype "passive"))
    )
    (net (code "129") (name "Net-(Q6-D)") (class "Default")
      (node (ref "LED_LL") (pin "3") (pinfunction "KB_3") (pintype "passive"))
      (node (ref "LED_LL") (pin "3-2") (pinfunction "KB_3-2") (pintype "passive"))
      (node (ref "LED_LR") (pin "3") (pinfunction "KB_3") (pintype "passive"))
      (node (ref "LED_LR") (pin "3-2") (pinfunction "KB_3-2") (pintype "passive"))
      (node (ref "LED_UL") (pin "3") (pinfunction "KB_3") (pintype "passive"))
      (node (ref "LED_UL") (pin "3-2") (pinfunction "KB_3-2") (pintype "passive"))
      (node (ref "LED_UR") (pin "3") (pinfunction "KB_3") (pintype "passive"))
      (node (ref "LED_UR") (pin "3-2") (pinfunction "KB_3-2") (pintype "passive"))
      (node (ref "Q6") (pin "3") (pinfunction "D_3") (pintype "passive"))
    )
    (net (code "130") (name "Net-(Q6-G)") (class "Default")
      (node (ref "Q6") (pin "1") (pinfunction "G_1") (pintype "passive"))
      (node (ref "R42") (pin "2") (pinfunction "2_2") (pintype "passive"))
    )
    (net (code "131") (name "Net-(R29-Pad2)") (class "Default")
      (node (ref "R29") (pin "2") (pinfunction "2_2") (pintype "passive"))
      (node (ref "STOP") (pin "P$1") (pinfunction "P$1_P$1") (pintype "bidirectional"))
    )
    (net (code "132") (name "Net-(R32-Pad2)") (class "Default")
      (node (ref "R32") (pin "2") (pinfunction "2_2") (pintype "passive"))
      (node (ref "VOL+") (pin "P$1") (pinfunction "P$1_P$1") (pintype "bidirectional"))
    )
    (net (code "133") (name "Net-(R33-Pad2)") (class "Default")
      (node (ref "R33") (pin "2") (pinfunction "2_2") (pintype "passive"))
      (node (ref "WIRELESS") (pin "P$1") (pinfunction "P$1_P$1") (pintype "bidirectional"))
    )
    (net (code "134") (name "Net-(R34-Pad2)") (class "Default")
      (node (ref "R34") (pin "2") (pinfunction "2_2") (pintype "passive"))
      (node (ref "VOL-") (pin "P$1") (pinfunction "P$1_P$1") (pintype "bidirectional"))
    )
    (net (code "135") (name "Net-(U1-ANT)") (class "Default")
      (node (ref "L4") (pin "1") (pinfunction "1_1") (pintype "passive"))
      (node (ref "U1") (pin "11") (pinfunction "ANT_11") (pintype "bidirectional"))
    )
    (net (code "136") (name "Net-(U1-BIAS)") (class "Default")
      (node (ref "R2") (pin "2") (pinfunction "2_2") (pintype "passive"))
      (node (ref "U1") (pin "15") (pinfunction "BIAS_15") (pintype "bidirectional"))
    )
    (net (code "137") (name "Net-(U1-HGM)") (class "Default")
      (node (ref "R1") (pin "1") (pinfunction "1_1") (pintype "passive"))
      (node (ref "U1") (pin "7") (pinfunction "HGM_7") (pintype "bidirectional"))
    )
    (net (code "138") (name "Net-(U2-AD0{slash}GIO7)") (class "Default")
      (node (ref "L11") (pin "2") (pinfunction "2_2") (pintype "passive"))
      (node (ref "U2") (pin "16") (pinfunction "AD0/GIO7_16") (pintype "bidirectional"))
    )
    (net (code "139") (name "Net-(U2-AD1{slash}GIO8)") (class "Default")
      (node (ref "L13") (pin "2") (pinfunction "2_2") (pintype "passive"))
      (node (ref "U2") (pin "17") (pinfunction "AD1/GIO8_17") (pintype "bidirectional"))
    )
    (net (code "140") (name "Net-(U2-BCLK{slash}GIO5)") (class "Default")
      (node (ref "L9") (pin "2") (pinfunction "2_2") (pintype "passive"))
      (node (ref "U2") (pin "14") (pinfunction "BCLK/GIO5_14") (pintype "bidirectional"))
    )
    (net (code "141") (name "Net-(U2-DCPL)") (class "Default")
      (node (ref "C25") (pin "1") (pinfunction "1_1") (pintype "passive"))
      (node (ref "U2") (pin "39") (pinfunction "DCPL_39") (pintype "bidirectional"))
    )
    (net (code "142") (name "Net-(U2-GIO3)") (class "Default")
      (node (ref "R4") (pin "1") (pinfunction "1_1") (pintype "passive"))
      (node (ref "U2") (pin "9") (pinfunction "GIO3_9") (pintype "bidirectional"))
    )
    (net (code "143") (name "Net-(U2-RBIAS)") (class "Default")
      (node (ref "R3") (pin "2") (pinfunction "2_2") (pintype "passive"))
      (node (ref "U2") (pin "30") (pinfunction "RBIAS_30") (pintype "bidirectional"))
    )
    (net (code "144") (name "Net-(U2-WCLK{slash}GIO6)") (class "Default")
      (node (ref "L10") (pin "2") (pinfunction "2_2") (pintype "passive"))
      (node (ref "U2") (pin "15") (pinfunction "WCLK/GIO6_15") (pintype "bidirectional"))
    )
    (net (code "145") (name "Net-(U2-X1)") (class "Default")
      (node (ref "U2") (pin "21") (pinfunction "X1_21") (pintype "bidirectional"))
      (node (ref "X3") (pin "3") (pinfunction "OUT_3") (pintype "bidirectional"))
    )
    (net (code "146") (name "Net-(U2-XPAEN)") (class "Default")
      (node (ref "L12") (pin "1") (pinfunction "1_1") (pintype "passive"))
      (node (ref "U2") (pin "36") (pinfunction "XPAEN_36") (pintype "bidirectional"))
    )
    (net (code "147") (name "Net-(U2-~{RESET})") (class "Default")
      (node (ref "L7") (pin "1") (pinfunction "1_1") (pintype "passive"))
      (node (ref "U2") (pin "11") (pinfunction "~{RESET}_11") (pintype "bidirectional"))
    )
    (net (code "148") (name "Net-(U3-AINA)") (class "Default")
      (node (ref "C36") (pin "2") (pinfunction "2_2") (pintype "passive"))
      (node (ref "U3") (pin "15") (pinfunction "AINA_15") (pintype "bidirectional"))
    )
    (net (code "149") (name "Net-(U3-AINB)") (class "Default")
      (node (ref "C38") (pin "2") (pinfunction "2_2") (pintype "passive"))
      (node (ref "U3") (pin "16") (pinfunction "AINB_16") (pintype "bidirectional"))
    )
    (net (code "150") (name "Net-(U3-FILT+)") (class "Default")
      (node (ref "C44") (pin "1") (pinfunction "1_1") (pintype "passive"))
      (node (ref "C45") (pin "1") (pinfunction "1_1") (pintype "passive"))
      (node (ref "U3") (pin "18") (pinfunction "FILT+_18") (pintype "bidirectional"))
    )
    (net (code "151") (name "Net-(U3-VQ)") (class "Default")
      (node (ref "C46") (pin "1") (pinfunction "1_1") (pintype "passive"))
      (node (ref "C47") (pin "1") (pinfunction "1_1") (pintype "passive"))
      (node (ref "U3") (pin "17") (pinfunction "VQ_17") (pintype "bidirectional"))
    )
    (net (code "152") (name "Net-(U4-BYPASS)") (class "Default")
      (node (ref "C63") (pin "1") (pinfunction "1_1") (pintype "passive"))
      (node (ref "U4") (pin "1") (pinfunction "BYPASS_1") (pintype "bidirectional"))
    )
    (net (code "153") (name "Net-(U4-INA)") (class "Default")
      (node (ref "R7") (pin "2") (pinfunction "2_2") (pintype "passive"))
      (node (ref "R9") (pin "1") (pinfunction "1_1") (pintype "passive"))
      (node (ref "U4") (pin "8") (pinfunction "INA_8") (pintype "bidirectional"))
    )
    (net (code "154") (name "Net-(U4-INB)") (class "Default")
      (node (ref "R14") (pin "1") (pinfunction "1_1") (pintype "passive"))
      (node (ref "R21") (pin "2") (pinfunction "2_2") (pintype "passive"))
      (node (ref "U4") (pin "4") (pinfunction "INB_4") (pintype "bidirectional"))
    )
    (net (code "155") (name "Net-(U4-OUTB)") (class "Default")
      (node (ref "C66") (pin "1") (pinfunction "1_1") (pintype "passive"))
      (node (ref "R21") (pin "1") (pinfunction "1_1") (pintype "passive"))
      (node (ref "U4") (pin "5") (pinfunction "OUTB_5") (pintype "bidirectional"))
    )
    (net (code "156") (name "Net-(U5-VIN)") (class "Default")
      (node (ref "F1") (pin "2") (pinfunction "2_2") (pintype "passive"))
      (node (ref "L21") (pin "2") (pinfunction "2_2") (pintype "passive"))
      (node (ref "U5") (pin "1") (pinfunction "VIN_1") (pintype "bidirectional"))
    )
    (net (code "157") (name "Net-(U6-ISET)") (class "Default")
      (node (ref "R38") (pin "2") (pinfunction "2_2") (pintype "passive"))
      (node (ref "U6") (pin "2") (pinfunction "ISET_2") (pintype "bidirectional"))
    )
    (net (code "158") (name "Net-(U6-PRETERM)") (class "Default")
      (node (ref "R39") (pin "2") (pinfunction "2_2") (pintype "passive"))
      (node (ref "U6") (pin "4") (pinfunction "PRETERM_4") (pintype "bidirectional"))
    )
    (net (code "159") (name "Net-(U6-TS)") (class "Default")
      (node (ref "R37") (pin "2") (pinfunction "2_2") (pintype "passive"))
      (node (ref "U6") (pin "9") (pinfunction "TS_9") (pintype "bidirectional"))
    )
    (net (code "160") (name "Net-(U6-~{CHG})") (class "Default")
      (node (ref "CHARGE") (pin "C") (pinfunction "C_C") (pintype "passive"))
      (node (ref "U6") (pin "8") (pinfunction "~{CHG}_8") (pintype "bidirectional"))
    )
    (net (code "161") (name "Net-(U7-EN)") (class "Default")
      (node (ref "C71") (pin "1") (pinfunction "1_1") (pintype "passive"))
      (node (ref "L21") (pin "1") (pinfunction "1_1") (pintype "passive"))
      (node (ref "U7") (pin "1") (pinfunction "VIN_1") (pintype "bidirectional"))
      (node (ref "U7") (pin "3") (pinfunction "EN_3") (pintype "bidirectional"))
    )
    (net (code "162") (name "Net-(U9-FILTP)") (class "Default")
      (node (ref "C82") (pin "1") (pinfunction "1_1") (pintype "passive"))
      (node (ref "U9") (pin "6") (pinfunction "FILTP_6") (pintype "bidirectional"))
    )
    (net (code "163") (name "Net-(U10D-D+_FS)") (class "Default")
      (node (ref "R15") (pin "1") (pinfunction "1_1") (pintype "passive"))
      (node (ref "U10") (pin "9") (pinfunction "D+_FS_9") (pintype "bidirectional"))
    )
    (net (code "164") (name "Net-(U10D-D-_FS)") (class "Default")
      (node (ref "R17") (pin "1") (pinfunction "1_1") (pintype "passive"))
      (node (ref "U10") (pin "8") (pinfunction "D-_FS_8") (pintype "bidirectional"))
    )
    (net (code "165") (name "Net-(U10D-USB_VBIAS)") (class "Default")
      (node (ref "C76") (pin "1") (pinfunction "1_1") (pintype "passive"))
      (node (ref "R27") (pin "2") (pinfunction "2_2") (pintype "passive"))
      (node (ref "U10") (pin "3") (pinfunction "USB_VBIAS_3") (pintype "bidirectional"))
    )
    (net (code "166") (name "Net-(U10E-VDDCORE)") (class "Default")
      (node (ref "C68") (pin "1") (pinfunction "1_1") (pintype "passive"))
      (node (ref "C69") (pin "1") (pinfunction "1_1") (pintype "passive"))
      (node (ref "U10") (pin "141") (pinfunction "VDDCORE_141") (pintype "bidirectional"))
    )
    (net (code "167") (name "Net-(U11-SNS0)") (class "Default")
      (node (ref "C87") (pin "1") (pinfunction "1_1") (pintype "passive"))
      (node (ref "U11") (pin "32") (pinfunction "SNS0_32") (pintype "bidirectional"))
    )
    (net (code "168") (name "Net-(U11-SNS0K)") (class "Default")
      (node (ref "C87") (pin "2") (pinfunction "2_2") (pintype "passive"))
      (node (ref "R29") (pin "1") (pinfunction "1_1") (pintype "passive"))
      (node (ref "U11") (pin "1") (pinfunction "SNS0K_1") (pintype "bidirectional"))
    )
    (net (code "169") (name "Net-(U11-SNS1)") (class "Default")
      (node (ref "C88") (pin "1") (pinfunction "1_1") (pintype "passive"))
      (node (ref "U11") (pin "2") (pinfunction "SNS1_2") (pintype "bidirectional"))
    )
    (net (code "170") (name "Net-(U11-SNS1K)") (class "Default")
      (node (ref "C88") (pin "2") (pinfunction "2_2") (pintype "passive"))
      (node (ref "R30") (pin "1") (pinfunction "1_1") (pintype "passive"))
      (node (ref "U11") (pin "3") (pinfunction "SNS1K_3") (pintype "bidirectional"))
    )
    (net (code "171") (name "Net-(U11-SNS2)") (class "Default")
      (node (ref "C89") (pin "1") (pinfunction "1_1") (pintype "passive"))
      (node (ref "U11") (pin "7") (pinfunction "SNS2_7") (pintype "bidirectional"))
    )
    (net (code "172") (name "Net-(U11-SNS2K)") (class "Default")
      (node (ref "C89") (pin "2") (pinfunction "2_2") (pintype "passive"))
      (node (ref "R31") (pin "1") (pinfunction "1_1") (pintype "passive"))
      (node (ref "U11") (pin "6") (pinfunction "SNS2K_6") (pintype "bidirectional"))
    )
    (net (code "173") (name "Net-(U11-SNS3)") (class "Default")
      (node (ref "C90") (pin "1") (pinfunction "1_1") (pintype "passive"))
      (node (ref "U11") (pin "8") (pinfunction "SNS3_8") (pintype "bidirectional"))
    )
    (net (code "174") (name "Net-(U11-SNS3K)") (class "Default")
      (node (ref "C90") (pin "2") (pinfunction "2_2") (pintype "passive"))
      (node (ref "R32") (pin "1") (pinfunction "1_1") (pintype "passive"))
      (node (ref "U11") (pin "9") (pinfunction "SNS3K_9") (pintype "bidirectional"))
    )
    (net (code "175") (name "Net-(U11-SNS4)") (class "Default")
      (node (ref "C91") (pin "1") (pinfunction "1_1") (pintype "passive"))
      (node (ref "U11") (pin "10") (pinfunction "SNS4_10") (pintype "bidirectional"))
    )
    (net (code "176") (name "Net-(U11-SNS4K)") (class "Default")
      (node (ref "C91") (pin "2") (pinfunction "2_2") (pintype "passive"))
      (node (ref "R33") (pin "1") (pinfunction "1_1") (pintype "passive"))
      (node (ref "U11") (pin "11") (pinfunction "SNS4K_11") (pintype "bidirectional"))
    )
    (net (code "177") (name "Net-(U11-SNS5)") (class "Default")
      (node (ref "C92") (pin "1") (pinfunction "1_1") (pintype "passive"))
      (node (ref "U11") (pin "12") (pinfunction "SNS5_12") (pintype "bidirectional"))
    )
    (net (code "178") (name "Net-(U11-SNS5K)") (class "Default")
      (node (ref "C92") (pin "2") (pinfunction "2_2") (pintype "passive"))
      (node (ref "R34") (pin "1") (pinfunction "1_1") (pintype "passive"))
      (node (ref "U11") (pin "13") (pinfunction "SNS5K_13") (pintype "bidirectional"))
    )
    (net (code "179") (name "Net-(U11-SNS6)") (class "Default")
      (node (ref "C93") (pin "1") (pinfunction "1_1") (pintype "passive"))
      (node (ref "U11") (pin "20") (pinfunction "SNS6_20") (pintype "bidirectional"))
    )
    (net (code "180") (name "Net-(U11-SNS6K)") (class "Default")
      (node (ref "C93") (pin "2") (pinfunction "2_2") (pintype "passive"))
      (node (ref "R35") (pin "1") (pinfunction "1_1") (pintype "passive"))
      (node (ref "U11") (pin "19") (pinfunction "SNS6K_19") (pintype "bidirectional"))
    )
    (net (code "181") (name "Net-(U11-SNS7K{slash}DETECT0)") (class "Default")
      (node (ref "C94") (pin "2") (pinfunction "2_2") (pintype "passive"))
      (node (ref "R36") (pin "1") (pinfunction "1_1") (pintype "passive"))
      (node (ref "U11") (pin "22") (pinfunction "SNS7K/DETECT0_22") (pintype "bidirectional"))
    )
    (net (code "182") (name "Net-(U11-SNS7{slash}DETECT1)") (class "Default")
      (node (ref "C94") (pin "1") (pinfunction "1_1") (pintype "passive"))
      (node (ref "U11") (pin "23") (pinfunction "SNS7/DETECT1_23") (pintype "bidirectional"))
    )
    (net (code "183") (name "Net-(U11-~{RESET})") (class "Default")
      (node (ref "R28") (pin "1") (pinfunction "1_1") (pintype "passive"))
      (node (ref "U11") (pin "29") (pinfunction "~{RESET}_29") (pintype "bidirectional"))
    )
    (net (code "184") (name "OUT_L") (class "Default")
      (node (ref "R41") (pin "2") (pinfunction "2_2") (pintype "passive"))
      (node (ref "U3") (pin "23") (pinfunction "OUTB_23") (pintype "bidirectional"))
    )
    (net (code "185") (name "OUT_R") (class "Default")
      (node (ref "R40") (pin "2") (pinfunction "2_2") (pintype "passive"))
      (node (ref "U3") (pin "22") (pinfunction "OUTA_22") (pintype "bidirectional"))
    )
    (net (code "186") (name "PA_EN") (class "Default")
      (node (ref "L12") (pin "2") (pinfunction "2_2") (pintype "passive"))
      (node (ref "R6") (pin "2") (pinfunction "2_2") (pintype "passive"))
      (node (ref "U1") (pin "5") (pinfunction "PAEN_5") (pintype "bidirectional"))
    )
    (net (code "187") (name "PHONE_L") (class "Default")
      (node (ref "C53") (pin "2") (pinfunction "2_2") (pintype "passive"))
      (node (ref "PHONE_OUT") (pin "4") (pinfunction "L_4") (pintype "bidirectional"))
      (node (ref "R25") (pin "2") (pinfunction "2_2") (pintype "passive"))
    )
    (net (code "188") (name "PHONE_R") (class "Default")
      (node (ref "C66") (pin "2") (pinfunction "2_2") (pintype "passive"))
      (node (ref "PHONE_OUT") (pin "1") (pinfunction "R_1") (pintype "bidirectional"))
    )
    (net (code "189") (name "PHONE_SENSE") (class "Default")
      (node (ref "PHONE_OUT") (pin "3") (pinfunction "L_SW_3") (pintype "bidirectional"))
      (node (ref "R16") (pin "1") (pinfunction "1_1") (pintype "passive"))
      (node (ref "U10") (pin "110") (pinfunction "PA22_110") (pintype "bidirectional"))
    )
    (net (code "190") (name "RED") (class "Default")
      (node (ref "TO_AUX1") (pin "3") (pinfunction "3_3") (pintype "bidirectional"))
      (node (ref "U10") (pin "132") (pinfunction "PA12_132") (pintype "bidirectional"))
    )
    (net (code "191") (name "RF_N") (class "Default")
      (node (ref "U1") (pin "2") (pinfunction "RF_N_2") (pintype "bidirectional"))
      (node (ref "U2") (pin "25") (pinfunction "RF_N_25") (pintype "bidirectional"))
    )
    (net (code "192") (name "RF_P") (class "Default")
      (node (ref "U1") (pin "4") (pinfunction "RF_P_4") (pintype "bidirectional"))
      (node (ref "U2") (pin "24") (pinfunction "RF_P_24") (pintype "bidirectional"))
    )
    (net (code "193") (name "RXD") (class "Default")
      (node (ref "SERIAL") (pin "3") (pinfunction "3_3") (pintype "bidirectional"))
      (node (ref "U10") (pin "125") (pinfunction "PA03_125") (pintype "bidirectional"))
    )
    (net (code "194") (name "SCLK0") (class "Default")
      (node (ref "CC_DEBUG") (pin "6") (pinfunction "6_6") (pintype "bidirectional"))
      (node (ref "U10") (pin "137") (pinfunction "PA08_137") (pintype "bidirectional"))
      (node (ref "U2") (pin "4") (pinfunction "SCLK_4") (pintype "bidirectional"))
      (node (ref "U9") (pin "9") (pinfunction "SCL/SCLK_9") (pintype "bidirectional"))
    )
    (net (code "195") (name "SCLK1") (class "Default")
      (node (ref "TO_AUX2") (pin "1") (pinfunction "1_1") (pintype "bidirectional"))
      (node (ref "U10") (pin "101") (pinfunction "PA15_101") (pintype "bidirectional"))
      (node (ref "U3") (pin "10") (pinfunction "SCL/SCLK_10") (pintype "bidirectional"))
    )
    (net (code "196") (name "SHDN") (class "Default")
      (node (ref "U10") (pin "111") (pinfunction "PA23_111") (pintype "bidirectional"))
      (node (ref "U4") (pin "3") (pinfunction "SHUTDOWN_3") (pintype "bidirectional"))
    )
    (net (code "197") (name "TCK") (class "Default")
      (node (ref "JTAG") (pin "1") (pinfunction "1_1") (pintype "bidirectional"))
      (node (ref "U10") (pin "107") (pinfunction "TCK_107") (pintype "bidirectional"))
    )
    (net (code "198") (name "TDI") (class "Default")
      (node (ref "JTAG") (pin "9") (pinfunction "9_9") (pintype "bidirectional"))
      (node (ref "U10") (pin "108") (pinfunction "TDI_108") (pintype "bidirectional"))
    )
    (net (code "199") (name "TDO") (class "Default")
      (node (ref "JTAG") (pin "3") (pinfunction "3_3") (pintype "bidirectional"))
      (node (ref "U10") (pin "105") (pinfunction "TDO_105") (pintype "bidirectional"))
    )
    (net (code "200") (name "TMS") (class "Default")
      (node (ref "JTAG") (pin "5") (pinfunction "5_5") (pintype "bidirectional"))
      (node (ref "U10") (pin "104") (pinfunction "TMS_104") (pintype "bidirectional"))
    )
    (net (code "201") (name "TXD") (class "Default")
      (node (ref "SERIAL") (pin "2") (pinfunction "2_2") (pintype "bidirectional"))
      (node (ref "U10") (pin "126") (pinfunction "PA04_126") (pintype "bidirectional"))
    )
    (net (code "202") (name "UC_MCLK") (class "Default")
      (node (ref "U10") (pin "13") (pinfunction "PC04_13") (pintype "bidirectional"))
      (node (ref "U8") (pin "1") (pinfunction "D_1") (pintype "bidirectional"))
      (node (ref "U8") (pin "4") (pinfunction "~{Q}_4") (pintype "bidirectional"))
    )
    (net (code "203") (name "UDQM") (class "Default")
      (node (ref "U10") (pin "67") (pinfunction "PX11_67") (pintype "bidirectional"))
      (node (ref "U13") (pin "39") (pinfunction "UDQM_39") (pintype "bidirectional"))
    )
    (net (code "204") (name "USBOTGID") (class "Default")
      (node (ref "U10") (pin "121") (pinfunction "PB05_121") (pintype "bidirectional"))
      (node (ref "USB") (pin "4") (pinfunction "ID_4") (pintype "bidirectional"))
    )
    (net (code "205") (name "WCLK") (class "Default")
      (node (ref "L10") (pin "1") (pinfunction "1_1") (pintype "passive"))
      (node (ref "U10") (pin "31") (pinfunction "PB11_31") (pintype "bidirectional"))
      (node (ref "U3") (pin "2") (pinfunction "WCLK_2") (pintype "bidirectional"))
    )
    (net (code "206") (name "unconnected-(CC_DEBUG-Pad3)") (class "Default")
      (node (ref "CC_DEBUG") (pin "3") (pinfunction "3_3") (pintype "bidirectional"))
    )
    (net (code "207") (name "unconnected-(CC_DEBUG-Pad4)") (class "Default")
      (node (ref "CC_DEBUG") (pin "4") (pinfunction "4_4") (pintype "bidirectional"))
    )
    (net (code "208") (name "unconnected-(CC_DEBUG-Pad9)") (class "Default")
      (node (ref "CC_DEBUG") (pin "9") (pinfunction "9_9") (pintype "bidirectional"))
    )
    (net (code "209") (name "unconnected-(GPIO-Pad1)") (class "Default")
      (node (ref "GPIO") (pin "1") (pinfunction "1_1") (pintype "bidirectional"))
    )
    (net (code "210") (name "unconnected-(GPIO-Pad3)") (class "Default")
      (node (ref "GPIO") (pin "3") (pinfunction "3_3") (pintype "bidirectional"))
    )
    (net (code "211") (name "unconnected-(JTAG-Pad7)") (class "Default")
      (node (ref "JTAG") (pin "7") (pinfunction "7_7") (pintype "bidirectional"))
    )
    (net (code "212") (name "unconnected-(JTAG-Pad8)") (class "Default")
      (node (ref "JTAG") (pin "8") (pinfunction "8_8") (pintype "bidirectional"))
    )
    (net (code "213") (name "unconnected-(LINE_IN-R_SW-Pad2)") (class "Default")
      (node (ref "LINE_IN") (pin "2") (pinfunction "R_SW_2") (pintype "bidirectional"))
    )
    (net (code "214") (name "unconnected-(PHONE_OUT-R_SW-Pad2)") (class "Default")
      (node (ref "PHONE_OUT") (pin "2") (pinfunction "R_SW_2") (pintype "bidirectional"))
    )
    (net (code "215") (name "unconnected-(RESET-Pad2)") (class "Default")
      (node (ref "RESET") (pin "2") (pinfunction "2_2") (pintype "bidirectional"))
    )
    (net (code "216") (name "unconnected-(RESET-Pad4)") (class "Default")
      (node (ref "RESET") (pin "4") (pinfunction "4_4") (pintype "bidirectional"))
    )
    (net (code "217") (name "unconnected-(SERIAL-Pad1)") (class "Default")
      (node (ref "SERIAL") (pin "1") (pinfunction "1_1") (pintype "bidirectional"))
    )
    (net (code "218") (name "unconnected-(SERIAL-Pad4)") (class "Default")
      (node (ref "SERIAL") (pin "4") (pinfunction "4_4") (pintype "bidirectional"))
    )
    (net (code "219") (name "unconnected-(SERIAL-Pad5)") (class "Default")
      (node (ref "SERIAL") (pin "5") (pinfunction "5_5") (pintype "bidirectional"))
    )
    (net (code "220") (name "unconnected-(U1-RXTX-Pad3)") (class "Default")
      (node (ref "U1") (pin "3") (pinfunction "RXTX_3") (pintype "bidirectional"))
    )
    (net (code "221") (name "unconnected-(U2-GIO2-Pad8)") (class "Default")
      (node (ref "U2") (pin "8") (pinfunction "GIO2_8") (pintype "bidirectional"))
    )
    (net (code "222") (name "unconnected-(U2-MCLK{slash}GIO4-Pad13)") (class "Default")
      (node (ref "U2") (pin "13") (pinfunction "MCLK/GIO4_13") (pintype "bidirectional"))
    )
    (net (code "223") (name "unconnected-(U2-USBN{slash}XANTN-Pad1)") (class "Default")
      (node (ref "U2") (pin "1") (pinfunction "USBN/XANTN_1") (pintype "bidirectional"))
    )
    (net (code "224") (name "unconnected-(U2-USBP{slash}XANTP-Pad2)") (class "Default")
      (node (ref "U2") (pin "2") (pinfunction "USBP/XANTP_2") (pintype "bidirectional"))
    )
    (net (code "225") (name "unconnected-(U2-X0-Pad22)") (class "Default")
      (node (ref "U2") (pin "22") (pinfunction "X0_22") (pintype "bidirectional"))
    )
    (net (code "226") (name "unconnected-(U3-AD2-Pad13)") (class "Default")
      (node (ref "U3") (pin "13") (pinfunction "AD2_13") (pintype "bidirectional"))
    )
    (net (code "227") (name "unconnected-(U6-~{PG}-Pad5)") (class "Default")
      (node (ref "U6") (pin "5") (pinfunction "~{PG}_5") (pintype "bidirectional"))
    )
    (net (code "228") (name "unconnected-(U9-AUX_OUT-Pad4)") (class "Default")
      (node (ref "U9") (pin "4") (pinfunction "AUX_OUT_4") (pintype "bidirectional"))
    )
    (net (code "229") (name "unconnected-(U10A-PA01-Pad123)") (class "Default")
      (node (ref "U10") (pin "123") (pinfunction "PA01_123") (pintype "bidirectional"))
    )
    (net (code "230") (name "unconnected-(U10A-PA02-Pad15)") (class "Default")
      (node (ref "U10") (pin "15") (pinfunction "PA02_15") (pintype "bidirectional"))
    )
    (net (code "231") (name "unconnected-(U10A-PA05-Pad124)") (class "Default")
      (node (ref "U10") (pin "124") (pinfunction "PA05_124") (pintype "bidirectional"))
    )
    (net (code "232") (name "unconnected-(U10A-PA14-Pad100)") (class "Default")
      (node (ref "U10") (pin "100") (pinfunction "PA14_100") (pintype "bidirectional"))
    )
    (net (code "233") (name "unconnected-(U10A-PA26-Pad120)") (class "Default")
      (node (ref "U10") (pin "120") (pinfunction "PA26_120") (pintype "bidirectional"))
    )
    (net (code "234") (name "unconnected-(U10B-PB02-Pad25)") (class "Default")
      (node (ref "U10") (pin "25") (pinfunction "PB02_25") (pintype "bidirectional"))
    )
    (net (code "235") (name "unconnected-(U10B-PB03-Pad24)") (class "Default")
      (node (ref "U10") (pin "24") (pinfunction "PB03_24") (pintype "bidirectional"))
    )
    (net (code "236") (name "unconnected-(U10B-PB04-Pad22)") (class "Default")
      (node (ref "U10") (pin "22") (pinfunction "PB04_22") (pintype "bidirectional"))
    )
    (net (code "237") (name "unconnected-(U10B-PB10-Pad16)") (class "Default")
      (node (ref "U10") (pin "16") (pinfunction "PB10_16") (pintype "bidirectional"))
    )
    (net (code "238") (name "unconnected-(U10C-PC00-Pad98)") (class "Default")
      (node (ref "U10") (pin "98") (pinfunction "PC00_98") (pintype "bidirectional"))
    )
    (net (code "239") (name "unconnected-(U10C-PC01-Pad99)") (class "Default")
      (node (ref "U10") (pin "99") (pinfunction "PC01_99") (pintype "bidirectional"))
    )
    (net (code "240") (name "unconnected-(U10C-PC03-Pad19)") (class "Default")
      (node (ref "U10") (pin "19") (pinfunction "PC03_19") (pintype "bidirectional"))
    )
    (net (code "241") (name "unconnected-(U10C-PC05-Pad12)") (class "Default")
      (node (ref "U10") (pin "12") (pinfunction "PC05_12") (pintype "bidirectional"))
    )
    (net (code "242") (name "unconnected-(U10F-PX12-Pad34)") (class "Default")
      (node (ref "U10") (pin "34") (pinfunction "PX12_34") (pintype "bidirectional"))
    )
    (net (code "243") (name "unconnected-(U10F-PX13-Pad33)") (class "Default")
      (node (ref "U10") (pin "33") (pinfunction "PX13_33") (pintype "bidirectional"))
    )
    (net (code "244") (name "unconnected-(U10F-PX15-Pad40)") (class "Default")
      (node (ref "U10") (pin "40") (pinfunction "PX15_40") (pintype "bidirectional"))
    )
    (net (code "245") (name "unconnected-(U10F-PX16-Pad32)") (class "Default")
      (node (ref "U10") (pin "32") (pinfunction "PX16_32") (pintype "bidirectional"))
    )
    (net (code "246") (name "unconnected-(U10F-PX22-Pad72)") (class "Default")
      (node (ref "U10") (pin "72") (pinfunction "PX22_72") (pintype "bidirectional"))
    )
    (net (code "247") (name "unconnected-(U10F-PX33-Pad95)") (class "Default")
      (node (ref "U10") (pin "95") (pinfunction "PX33_95") (pintype "bidirectional"))
    )
    (net (code "248") (name "unconnected-(U10F-PX40-Pad36)") (class "Default")
      (node (ref "U10") (pin "36") (pinfunction "PX40_36") (pintype "bidirectional"))
    )
    (net (code "249") (name "unconnected-(U10F-PX47-Pad39)") (class "Default")
      (node (ref "U10") (pin "39") (pinfunction "PX47_39") (pintype "bidirectional"))
    )
    (net (code "250") (name "unconnected-(U10F-PX48-Pad41)") (class "Default")
      (node (ref "U10") (pin "41") (pinfunction "PX48_41") (pintype "bidirectional"))
    )
    (net (code "251") (name "unconnected-(U10F-PX49-Pad43)") (class "Default")
      (node (ref "U10") (pin "43") (pinfunction "PX49_43") (pintype "bidirectional"))
    )
    (net (code "252") (name "unconnected-(U10F-PX50-Pad75)") (class "Default")
      (node (ref "U10") (pin "75") (pinfunction "PX50_75") (pintype "bidirectional"))
    )
    (net (code "253") (name "unconnected-(U10F-PX51-Pad77)") (class "Default")
      (node (ref "U10") (pin "77") (pinfunction "PX51_77") (pintype "bidirectional"))
    )
    (net (code "254") (name "unconnected-(U10F-PX52-Pad87)") (class "Default")
      (node (ref "U10") (pin "87") (pinfunction "PX52_87") (pintype "bidirectional"))
    )
    (net (code "255") (name "unconnected-(U10F-PX53-Pad42)") (class "Default")
      (node (ref "U10") (pin "42") (pinfunction "PX53_42") (pintype "bidirectional"))
    )
    (net (code "256") (name "unconnected-(U10F-PX54-Pad46)") (class "Default")
      (node (ref "U10") (pin "46") (pinfunction "PX54_46") (pintype "bidirectional"))
    )
    (net (code "257") (name "unconnected-(U10F-PX55-Pad79)") (class "Default")
      (node (ref "U10") (pin "79") (pinfunction "PX55_79") (pintype "bidirectional"))
    )
    (net (code "258") (name "unconnected-(U10F-PX56-Pad78)") (class "Default")
      (node (ref "U10") (pin "78") (pinfunction "PX56_78") (pintype "bidirectional"))
    )
    (net (code "259") (name "unconnected-(U10F-PX57-Pad76)") (class "Default")
      (node (ref "U10") (pin "76") (pinfunction "PX57_76") (pintype "bidirectional"))
    )
    (net (code "260") (name "unconnected-(U10F-PX58-Pad57)") (class "Default")
      (node (ref "U10") (pin "57") (pinfunction "PX58_57") (pintype "bidirectional"))
    )
    (net (code "261") (name "unconnected-(U10F-PX59-Pad56)") (class "Default")
      (node (ref "U10") (pin "56") (pinfunction "PX59_56") (pintype "bidirectional"))
    )
    (net (code "262") (name "unconnected-(U11-SNS8K{slash}DETECT3-Pad25)") (class "Default")
      (node (ref "U11") (pin "25") (pinfunction "SNS8K/DETECT3_25") (pintype "bidirectional"))
    )
    (net (code "263") (name "unconnected-(U11-SNS8{slash}DETECT2-Pad24)") (class "Default")
      (node (ref "U11") (pin "24") (pinfunction "SNS8/DETECT2_24") (pintype "bidirectional"))
    )
    (net (code "264") (name "unconnected-(U11-SNS9K{slash}DETECT5-Pad27)") (class "Default")
      (node (ref "U11") (pin "27") (pinfunction "SNS9K/DETECT5_27") (pintype "bidirectional"))
    )
    (net (code "265") (name "unconnected-(U11-SNS9{slash}DETECT4-Pad26)") (class "Default")
      (node (ref "U11") (pin "26") (pinfunction "SNS9/DETECT4_26") (pintype "bidirectional"))
    )
    (net (code "266") (name "unconnected-(U11-SNS10K{slash}SYNC-Pad31)") (class "Default")
      (node (ref "U11") (pin "31") (pinfunction "SNS10K/SYNC_31") (pintype "bidirectional"))
    )
    (net (code "267") (name "unconnected-(U11-SNS10{slash}DETECT16-Pad30)") (class "Default")
      (node (ref "U11") (pin "30") (pinfunction "SNS10/DETECT16_30") (pintype "bidirectional"))
    )
    (net (code "268") (name "unconnected-(U13-NC{slash}RFU-Pad40)") (class "Default")
      (node (ref "U13") (pin "40") (pinfunction "NC/RFU_40") (pintype "bidirectional"))
    )
  )
)
